# Replicape_B1.net
KiCad netlist of a schematic drawn in EAGLE
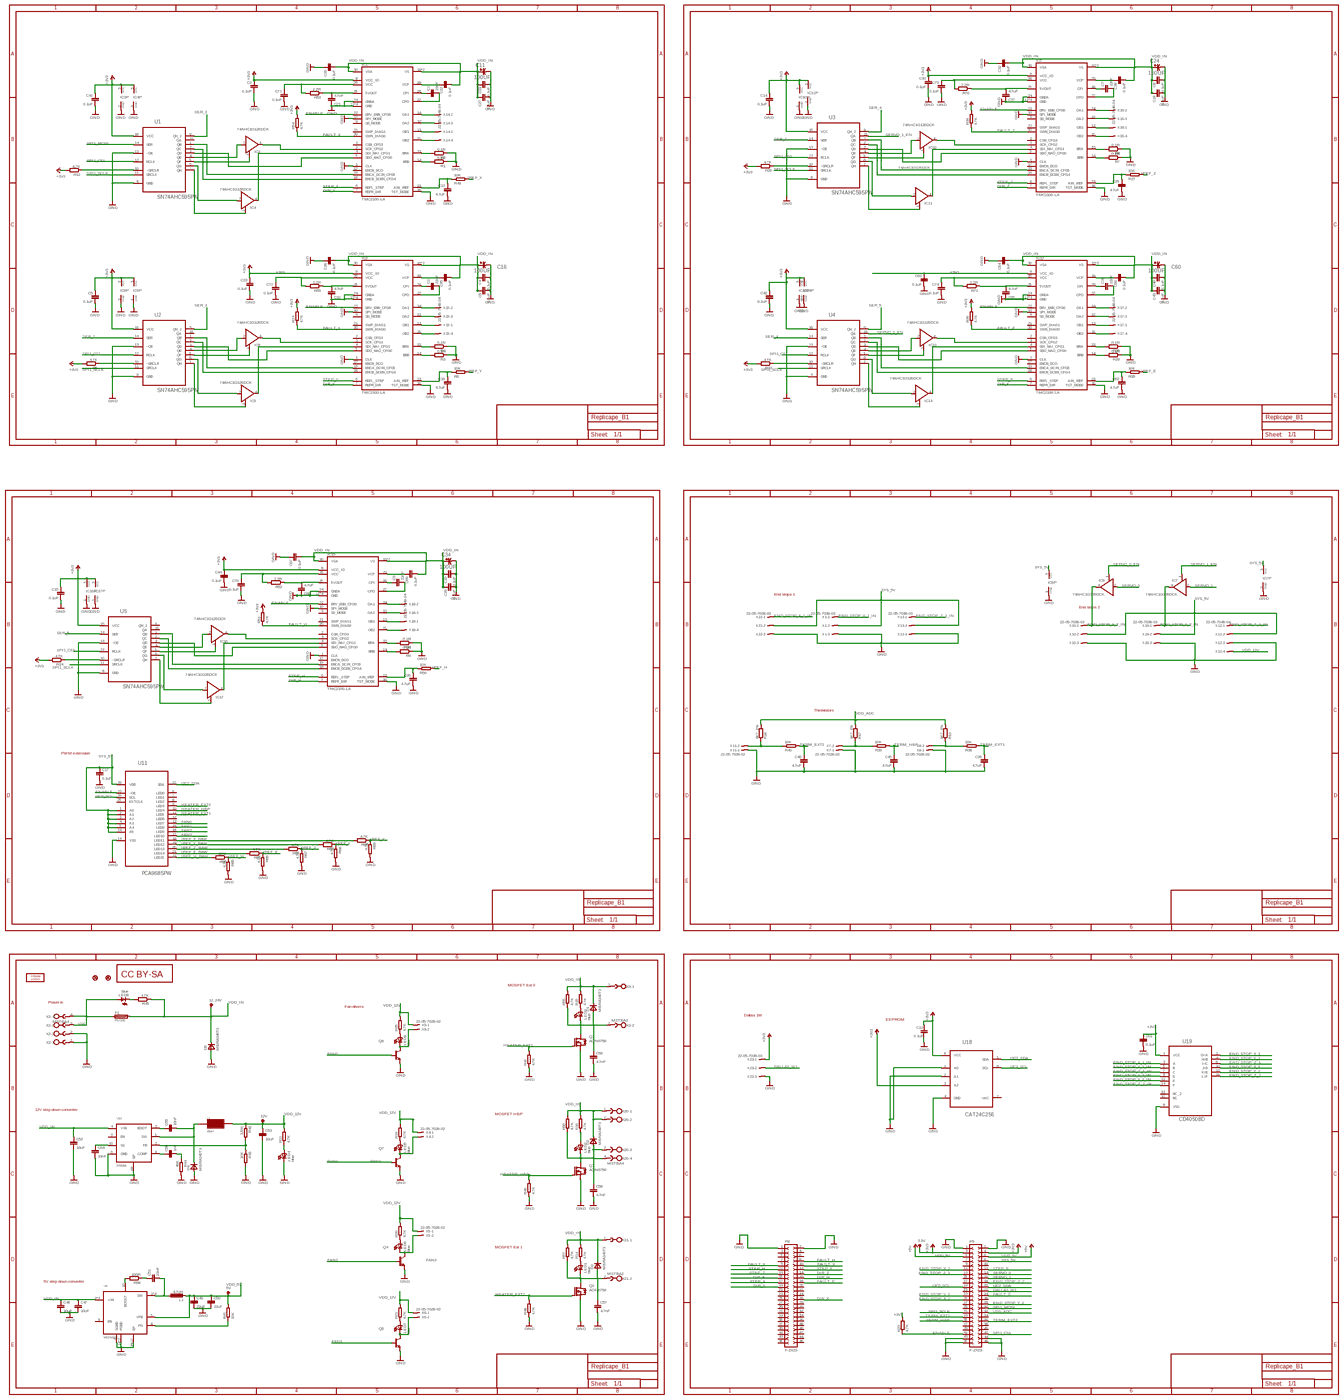
[diagram p0: schematic, sheet 1, overview]
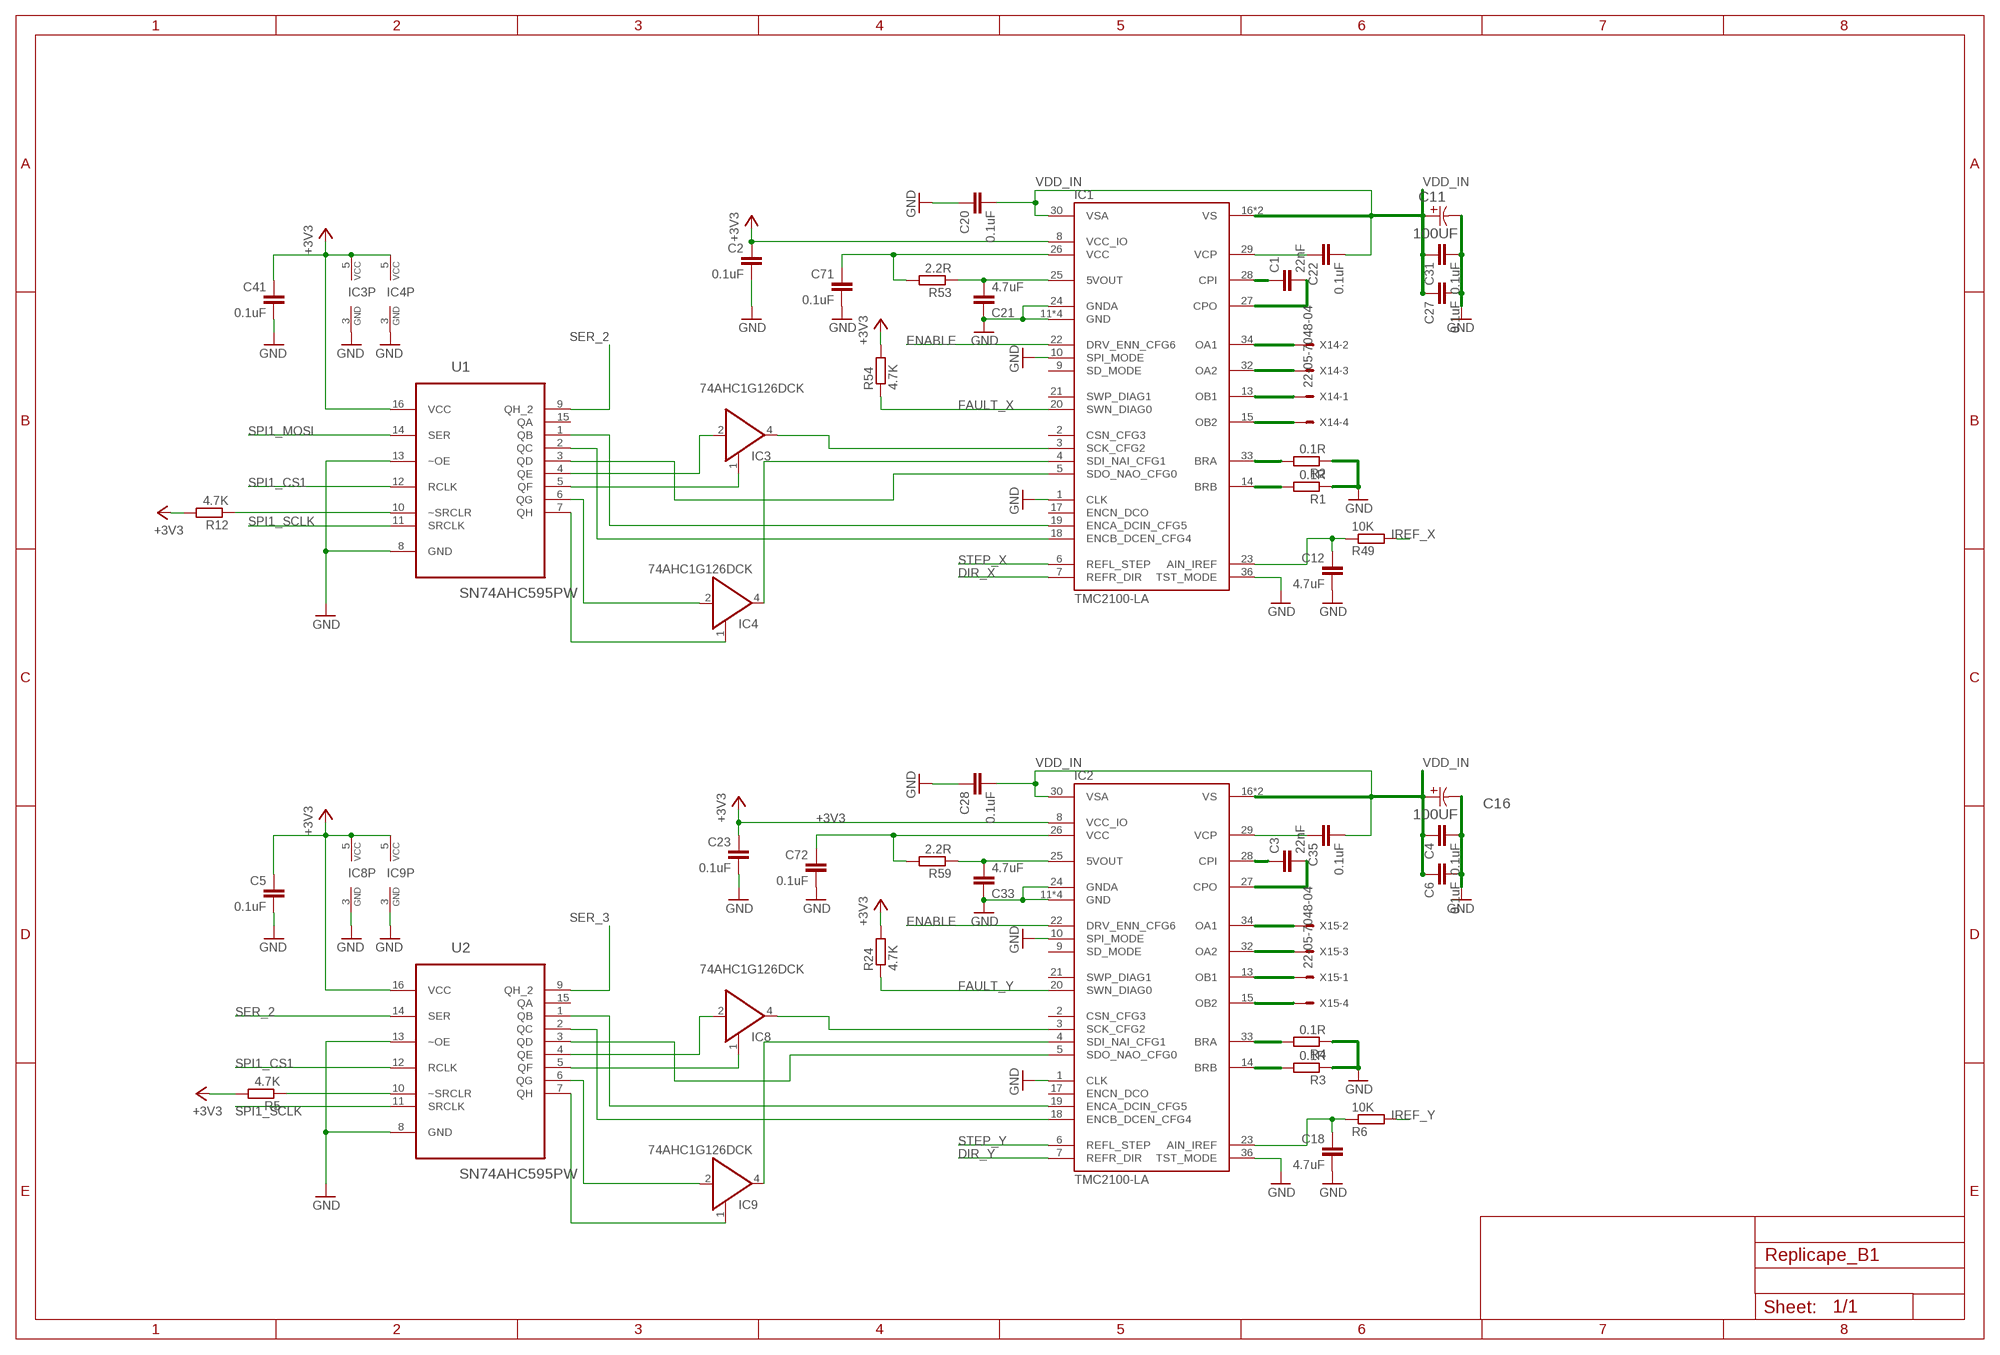
[diagram p1: schematic, sheet 1, part 1 of 4]
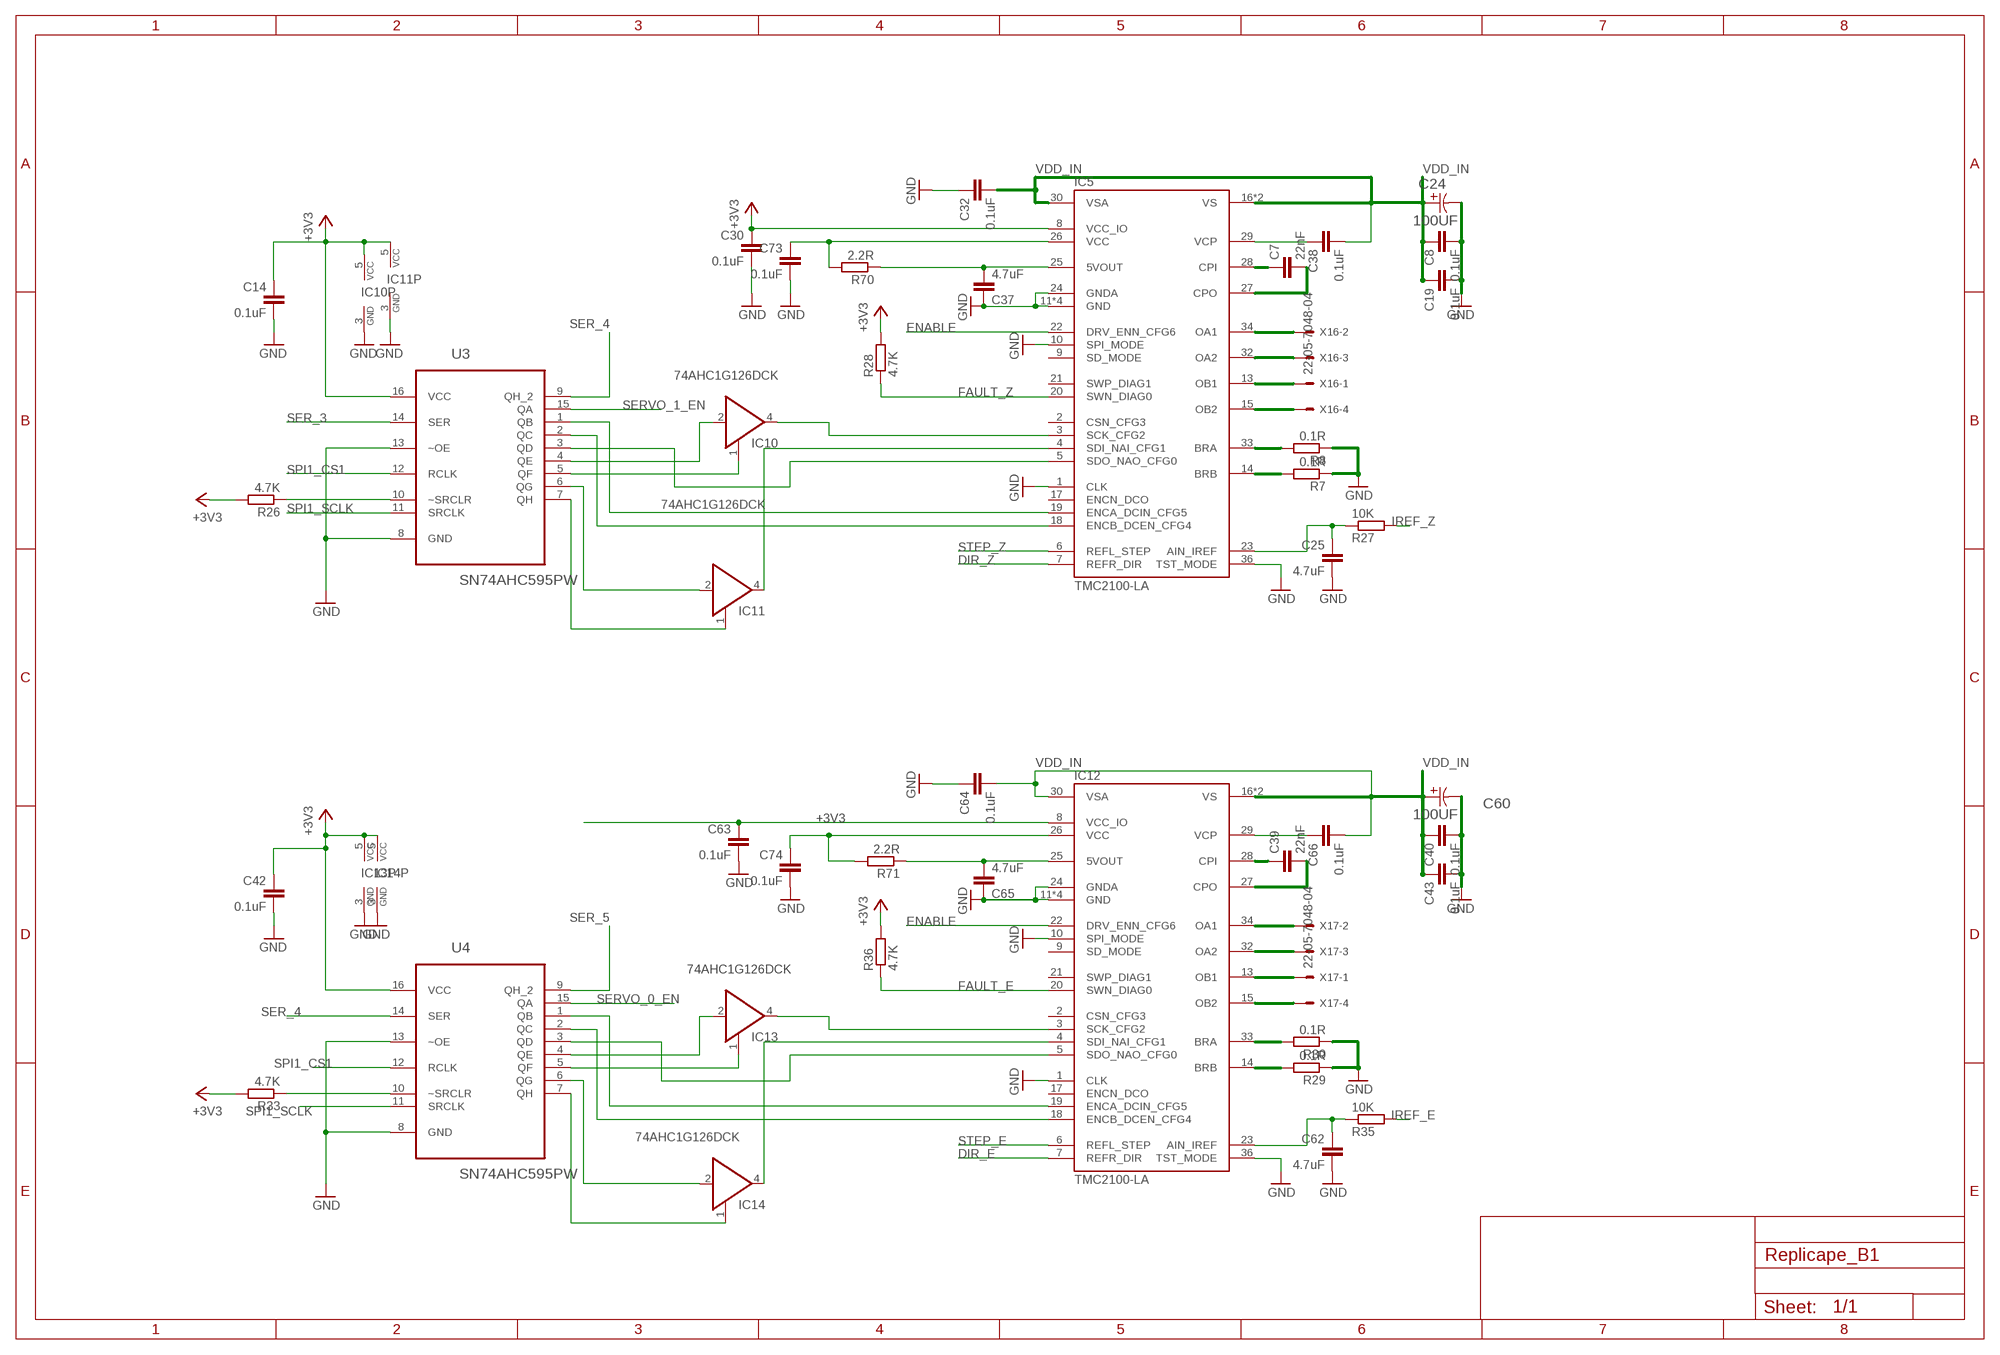
[diagram p2: schematic, sheet 1, part 2 of 4]
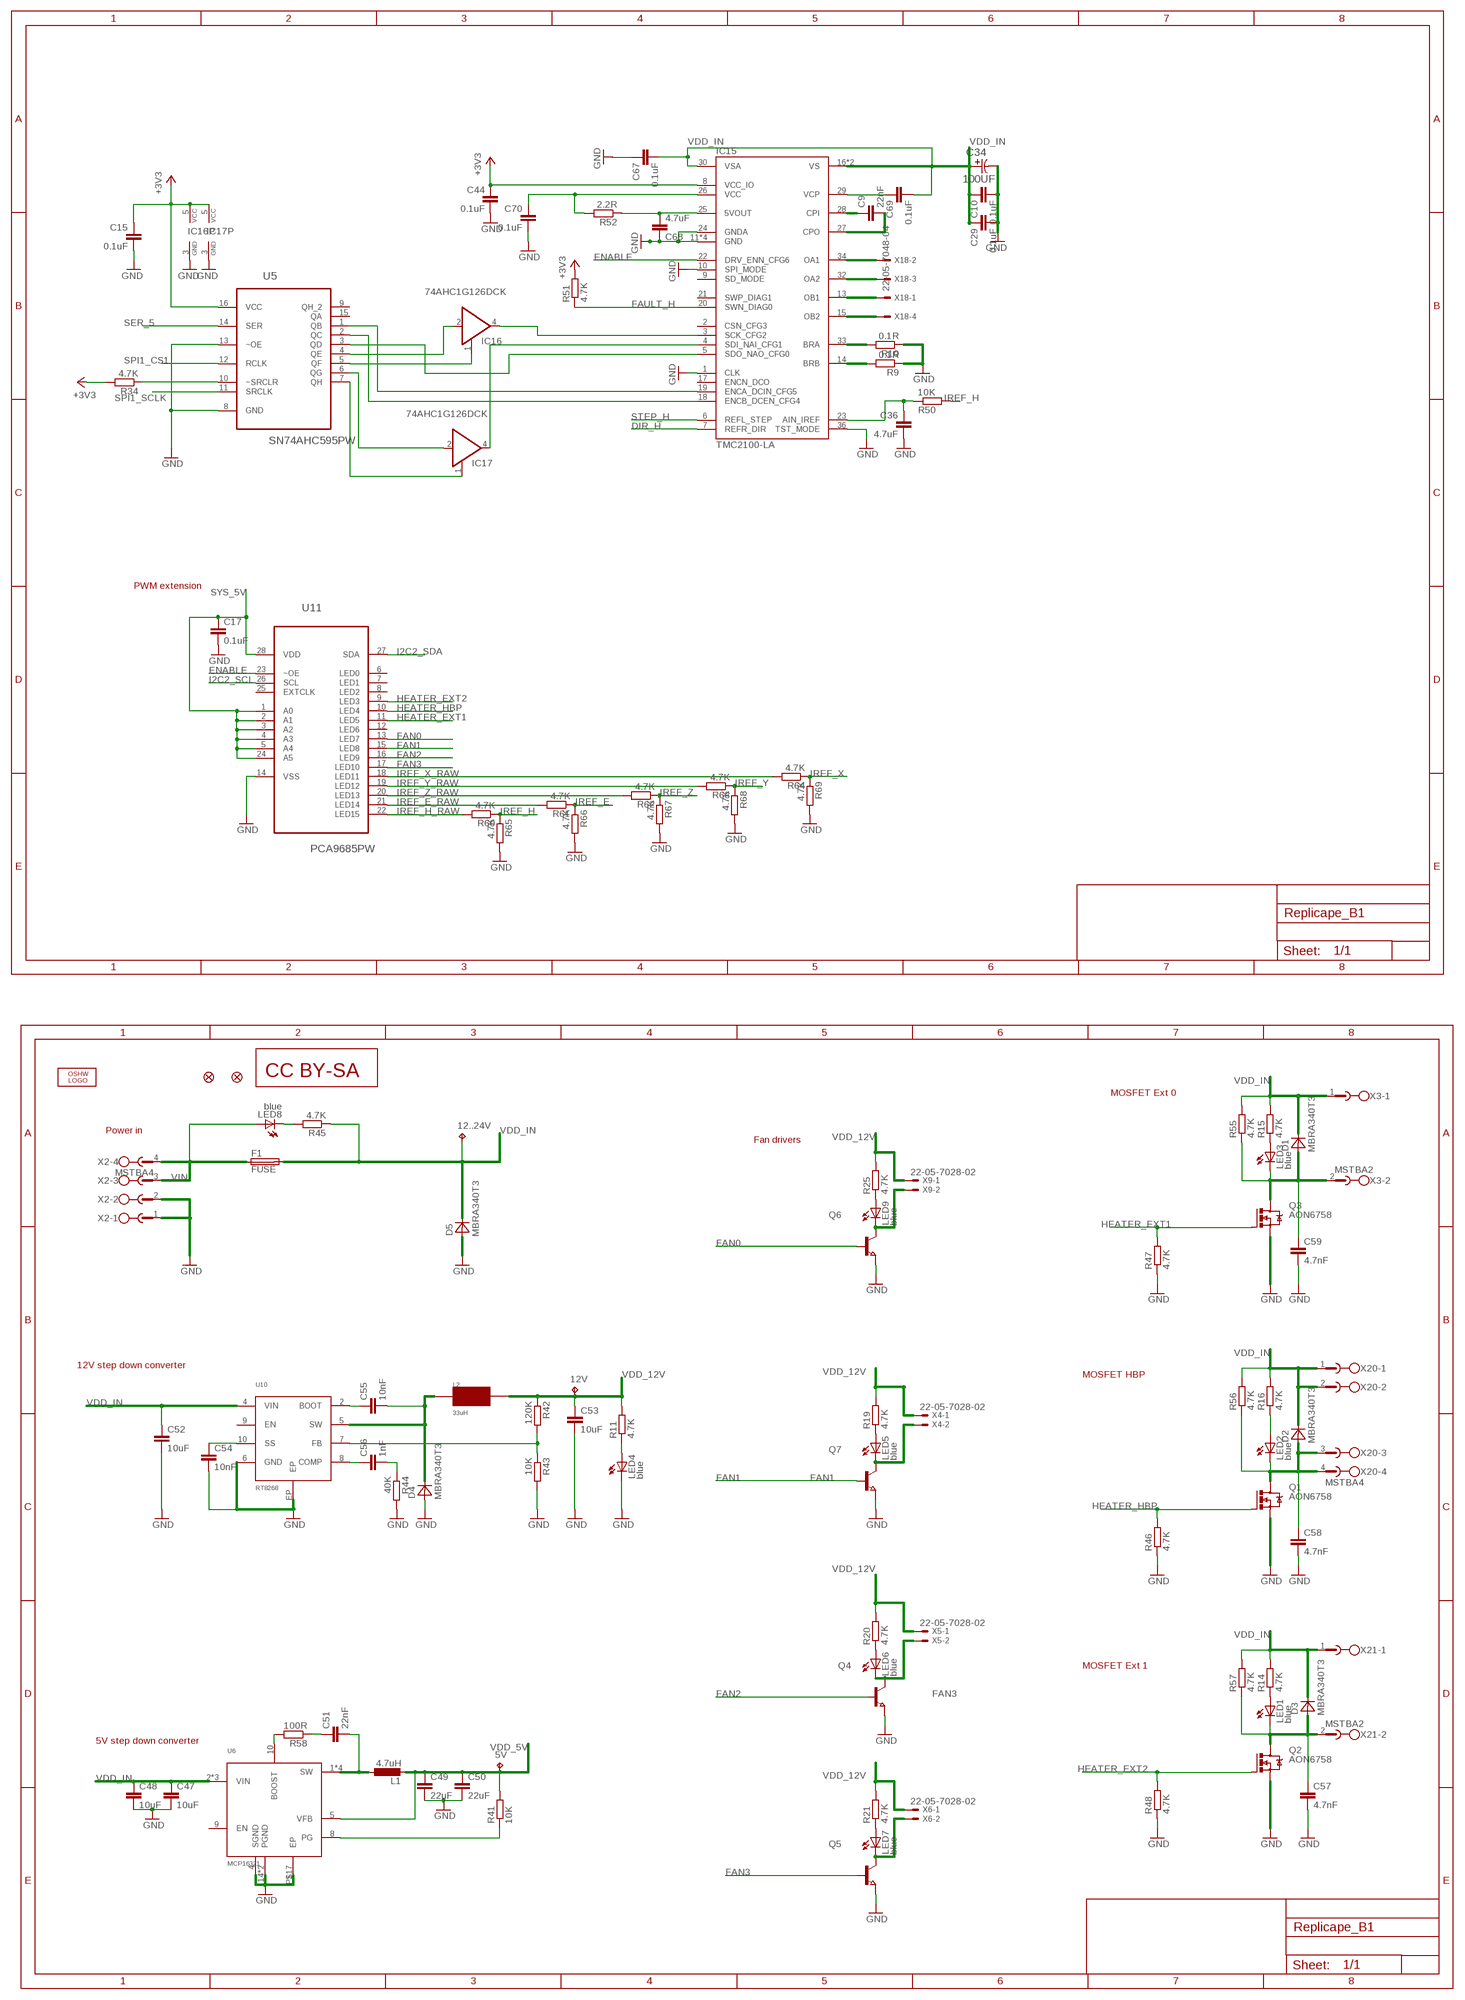
[diagram p3: schematic, sheet 1, part 3 of 4]
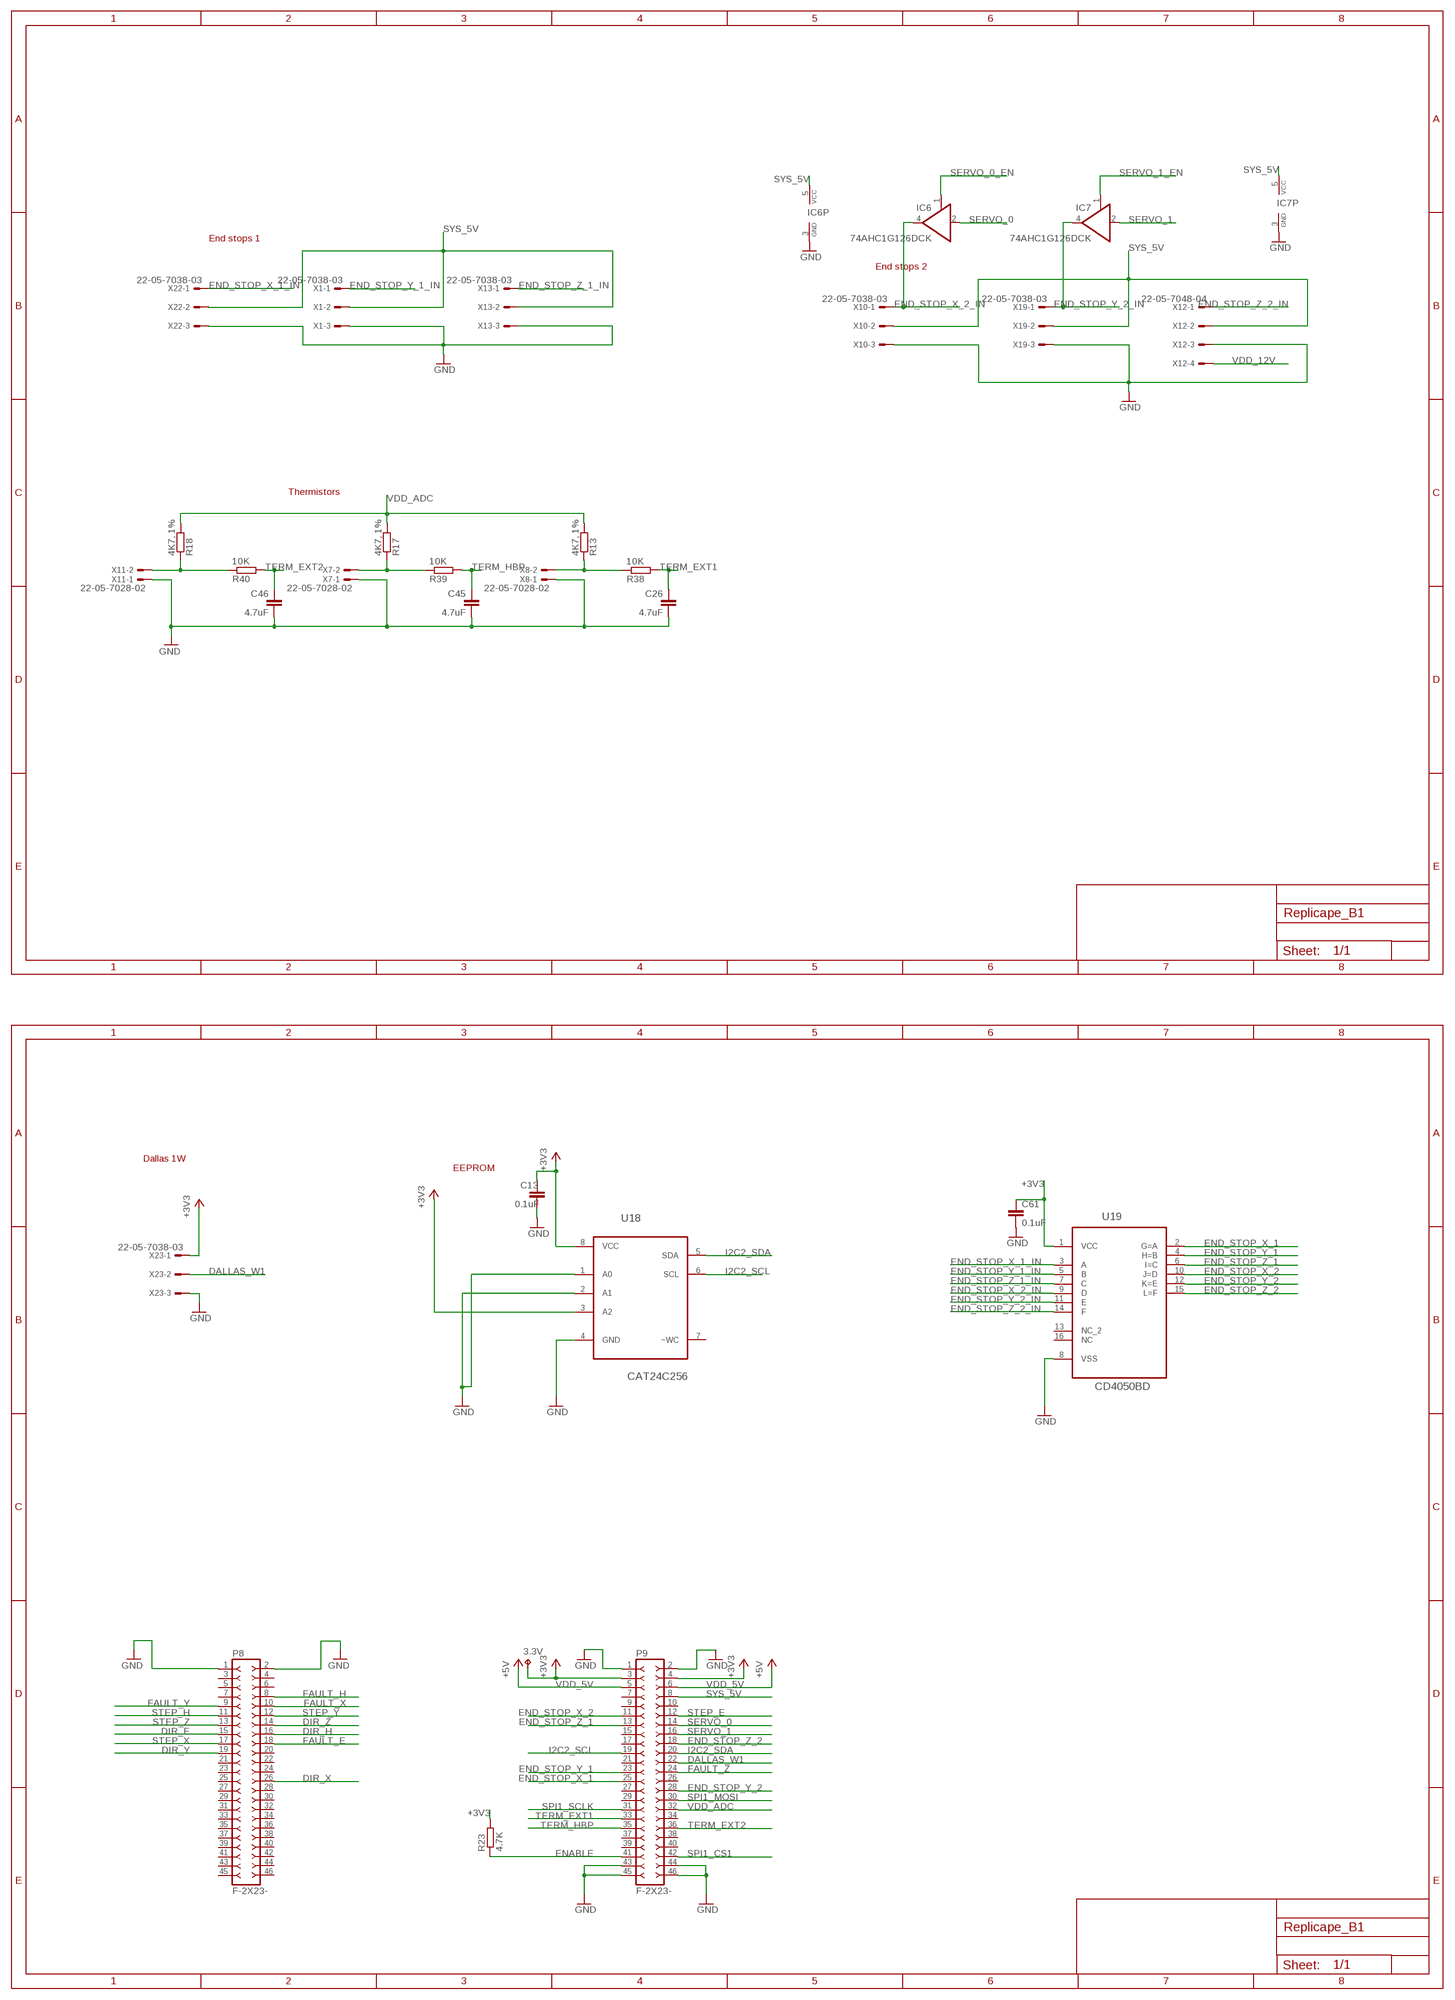
[diagram p4: schematic, sheet 1, part 4 of 4]

(export (version "E")
  (design (tool "Eeschema 10.0.6"))
  (components
    (comp (ref "3.3V")
      (value "TPB1,27")
      (footprint "eagle-import:B1,27")
      (libsource (lib "eagle-import") (part "TPB1,27"))
    )
    (comp (ref "5V")
      (value "TPB1,27")
      (footprint "eagle-import:B1,27")
      (libsource (lib "eagle-import") (part "TPB1,27"))
    )
    (comp (ref "12..24V")
      (value "TPB1,27")
      (footprint "eagle-import:B1,27")
      (libsource (lib "eagle-import") (part "TPB1,27"))
    )
    (comp (ref "12V")
      (value "TPB1,27")
      (footprint "eagle-import:B1,27")
      (libsource (lib "eagle-import") (part "TPB1,27"))
    )
    (comp (ref "C1")
      (value "22nF")
      (footprint "eagle-import:C0402")
      (libsource (lib "eagle-import") (part "C-EUC0402"))
    )
    (comp (ref "C2")
      (value "0.1uF")
      (footprint "eagle-import:C0402")
      (libsource (lib "eagle-import") (part "C-EUC0402"))
    )
    (comp (ref "C3")
      (value "22nF")
      (footprint "eagle-import:C0402")
      (libsource (lib "eagle-import") (part "C-EUC0402"))
    )
    (comp (ref "C4")
      (value "0.1uF")
      (footprint "eagle-import:C0402")
      (libsource (lib "eagle-import") (part "C-EUC0402"))
    )
    (comp (ref "C5")
      (value "0.1uF")
      (footprint "eagle-import:C0402")
      (libsource (lib "eagle-import") (part "C-EUC0402"))
    )
    (comp (ref "C6")
      (value "0.1uF")
      (footprint "eagle-import:C0402")
      (libsource (lib "eagle-import") (part "C-EUC0402"))
    )
    (comp (ref "C7")
      (value "22nF")
      (footprint "eagle-import:C0402")
      (libsource (lib "eagle-import") (part "C-EUC0402"))
    )
    (comp (ref "C8")
      (value "0.1uF")
      (footprint "eagle-import:C0402")
      (libsource (lib "eagle-import") (part "C-EUC0402"))
    )
    (comp (ref "C9")
      (value "22nF")
      (footprint "eagle-import:C0402")
      (libsource (lib "eagle-import") (part "C-EUC0402"))
    )
    (comp (ref "C10")
      (value "0.1uF")
      (footprint "eagle-import:C0402")
      (libsource (lib "eagle-import") (part "C-EUC0402"))
    )
    (comp (ref "C11")
      (value "100UF")
      (footprint "eagle-import:CAPAE660X800N")
      (fields (field (name "MPN") "EEE-FK1V101XP") (field (name "TOLERANCE") "±20 %"))
      (libsource (lib "eagle-import") (part "EEE--CASE-D8FK1V101XP"))
    )
    (comp (ref "C12")
      (value "4.7uF")
      (footprint "eagle-import:C0402")
      (libsource (lib "eagle-import") (part "C-EUC0402"))
    )
    (comp (ref "C13")
      (value "0.1uF")
      (footprint "eagle-import:C0402")
      (libsource (lib "eagle-import") (part "C-EUC0402"))
    )
    (comp (ref "C14")
      (value "0.1uF")
      (footprint "eagle-import:C0402")
      (libsource (lib "eagle-import") (part "C-EUC0402"))
    )
    (comp (ref "C15")
      (value "0.1uF")
      (footprint "eagle-import:C0402")
      (libsource (lib "eagle-import") (part "C-EUC0402"))
    )
    (comp (ref "C16")
      (value "100UF")
      (footprint "eagle-import:CAPAE660X800N")
      (fields (field (name "MPN") "EEE-FK1V101XP") (field (name "TOLERANCE") "±20 %"))
      (libsource (lib "eagle-import") (part "EEE--CASE-D8FK1V101XP"))
    )
    (comp (ref "C17")
      (value "0.1uF")
      (footprint "eagle-import:C0402")
      (libsource (lib "eagle-import") (part "C-EUC0402"))
    )
    (comp (ref "C18")
      (value "4.7uF")
      (footprint "eagle-import:C0402")
      (libsource (lib "eagle-import") (part "C-EUC0402"))
    )
    (comp (ref "C19")
      (value "0.1uF")
      (footprint "eagle-import:C0402")
      (libsource (lib "eagle-import") (part "C-EUC0402"))
    )
    (comp (ref "C20")
      (value "0.1uF")
      (footprint "eagle-import:C0402")
      (libsource (lib "eagle-import") (part "C-EUC0402"))
    )
    (comp (ref "C21")
      (value "4.7uF")
      (footprint "eagle-import:C0402")
      (libsource (lib "eagle-import") (part "C-EUC0402"))
    )
    (comp (ref "C22")
      (value "0.1uF")
      (footprint "eagle-import:C0402")
      (libsource (lib "eagle-import") (part "C-EUC0402"))
    )
    (comp (ref "C23")
      (value "0.1uF")
      (footprint "eagle-import:C0402")
      (libsource (lib "eagle-import") (part "C-EUC0402"))
    )
    (comp (ref "C24")
      (value "100UF")
      (footprint "eagle-import:CAPAE660X800N")
      (fields (field (name "MPN") "EEE-FK1V101XP") (field (name "TOLERANCE") "±20 %"))
      (libsource (lib "eagle-import") (part "EEE--CASE-D8FK1V101XP"))
    )
    (comp (ref "C25")
      (value "4.7uF")
      (footprint "eagle-import:C0402")
      (libsource (lib "eagle-import") (part "C-EUC0402"))
    )
    (comp (ref "C26")
      (value "4.7uF")
      (footprint "eagle-import:C0402")
      (libsource (lib "eagle-import") (part "C-EUC0402"))
    )
    (comp (ref "C27")
      (value "0.1uF")
      (footprint "eagle-import:C0402")
      (libsource (lib "eagle-import") (part "C-EUC0402"))
    )
    (comp (ref "C28")
      (value "0.1uF")
      (footprint "eagle-import:C0402")
      (libsource (lib "eagle-import") (part "C-EUC0402"))
    )
    (comp (ref "C29")
      (value "0.1uF")
      (footprint "eagle-import:C0402")
      (libsource (lib "eagle-import") (part "C-EUC0402"))
    )
    (comp (ref "C30")
      (value "0.1uF")
      (footprint "eagle-import:C0402")
      (libsource (lib "eagle-import") (part "C-EUC0402"))
    )
    (comp (ref "C31")
      (value "0.1uF")
      (footprint "eagle-import:C0402")
      (libsource (lib "eagle-import") (part "C-EUC0402"))
    )
    (comp (ref "C32")
      (value "0.1uF")
      (footprint "eagle-import:C0402")
      (libsource (lib "eagle-import") (part "C-EUC0402"))
    )
    (comp (ref "C33")
      (value "4.7uF")
      (footprint "eagle-import:C0402")
      (libsource (lib "eagle-import") (part "C-EUC0402"))
    )
    (comp (ref "C34")
      (value "100UF")
      (footprint "eagle-import:CAPAE660X800N")
      (fields (field (name "MPN") "EEE-FK1V101XP") (field (name "TOLERANCE") "±20 %"))
      (libsource (lib "eagle-import") (part "EEE--CASE-D8FK1V101XP"))
    )
    (comp (ref "C35")
      (value "0.1uF")
      (footprint "eagle-import:C0402")
      (libsource (lib "eagle-import") (part "C-EUC0402"))
    )
    (comp (ref "C36")
      (value "4.7uF")
      (footprint "eagle-import:C0402")
      (libsource (lib "eagle-import") (part "C-EUC0402"))
    )
    (comp (ref "C37")
      (value "4.7uF")
      (footprint "eagle-import:C0402")
      (libsource (lib "eagle-import") (part "C-EUC0402"))
    )
    (comp (ref "C38")
      (value "0.1uF")
      (footprint "eagle-import:C0402")
      (libsource (lib "eagle-import") (part "C-EUC0402"))
    )
    (comp (ref "C39")
      (value "22nF")
      (footprint "eagle-import:C0402")
      (libsource (lib "eagle-import") (part "C-EUC0402"))
    )
    (comp (ref "C40")
      (value "0.1uF")
      (footprint "eagle-import:C0402")
      (libsource (lib "eagle-import") (part "C-EUC0402"))
    )
    (comp (ref "C41")
      (value "0.1uF")
      (footprint "eagle-import:C0402")
      (libsource (lib "eagle-import") (part "C-EUC0402"))
    )
    (comp (ref "C42")
      (value "0.1uF")
      (footprint "eagle-import:C0402")
      (libsource (lib "eagle-import") (part "C-EUC0402"))
    )
    (comp (ref "C43")
      (value "0.1uF")
      (footprint "eagle-import:C0402")
      (libsource (lib "eagle-import") (part "C-EUC0402"))
    )
    (comp (ref "C44")
      (value "0.1uF")
      (footprint "eagle-import:C0402")
      (libsource (lib "eagle-import") (part "C-EUC0402"))
    )
    (comp (ref "C45")
      (value "4.7uF")
      (footprint "eagle-import:C0402")
      (libsource (lib "eagle-import") (part "C-EUC0402"))
    )
    (comp (ref "C46")
      (value "4.7uF")
      (footprint "eagle-import:C0402")
      (libsource (lib "eagle-import") (part "C-EUC0402"))
    )
    (comp (ref "C47")
      (value "10uF")
      (footprint "eagle-import:C1206")
      (libsource (lib "eagle-import") (part "C-EUC1206"))
    )
    (comp (ref "C48")
      (value "10uF")
      (footprint "eagle-import:C1206")
      (libsource (lib "eagle-import") (part "C-EUC1206"))
    )
    (comp (ref "C49")
      (value "22uF")
      (footprint "eagle-import:C1206")
      (libsource (lib "eagle-import") (part "C-EUC1206"))
    )
    (comp (ref "C50")
      (value "22uF")
      (footprint "eagle-import:C1206")
      (libsource (lib "eagle-import") (part "C-EUC1206"))
    )
    (comp (ref "C51")
      (value "22nF")
      (footprint "eagle-import:C0402")
      (libsource (lib "eagle-import") (part "C-EUC0402"))
    )
    (comp (ref "C52")
      (value "10uF")
      (footprint "eagle-import:C1206")
      (libsource (lib "eagle-import") (part "C-EUC1206"))
    )
    (comp (ref "C53")
      (value "10uF")
      (footprint "eagle-import:C1206")
      (libsource (lib "eagle-import") (part "C-EUC1206"))
    )
    (comp (ref "C54")
      (value "10nF")
      (footprint "eagle-import:C0402")
      (libsource (lib "eagle-import") (part "C-EUC0402"))
    )
    (comp (ref "C55")
      (value "10nF")
      (footprint "eagle-import:C0402")
      (libsource (lib "eagle-import") (part "C-EUC0402"))
    )
    (comp (ref "C56")
      (value "1nF")
      (footprint "eagle-import:C0402")
      (libsource (lib "eagle-import") (part "C-EUC0402"))
    )
    (comp (ref "C57")
      (value "4.7nF")
      (footprint "eagle-import:C0402")
      (libsource (lib "eagle-import") (part "C-EUC0402"))
    )
    (comp (ref "C58")
      (value "4.7nF")
      (footprint "eagle-import:C0402")
      (libsource (lib "eagle-import") (part "C-EUC0402"))
    )
    (comp (ref "C59")
      (value "4.7nF")
      (footprint "eagle-import:C0402")
      (libsource (lib "eagle-import") (part "C-EUC0402"))
    )
    (comp (ref "C60")
      (value "100UF")
      (footprint "eagle-import:CAPAE660X800N")
      (fields (field (name "MPN") "EEE-FK1V101XP") (field (name "TOLERANCE") "±20 %"))
      (libsource (lib "eagle-import") (part "EEE--CASE-D8FK1V101XP"))
    )
    (comp (ref "C61")
      (value "0.1uF")
      (footprint "eagle-import:C0402")
      (libsource (lib "eagle-import") (part "C-EUC0402"))
    )
    (comp (ref "C62")
      (value "4.7uF")
      (footprint "eagle-import:C0402")
      (libsource (lib "eagle-import") (part "C-EUC0402"))
    )
    (comp (ref "C63")
      (value "0.1uF")
      (footprint "eagle-import:C0402")
      (libsource (lib "eagle-import") (part "C-EUC0402"))
    )
    (comp (ref "C64")
      (value "0.1uF")
      (footprint "eagle-import:C0402")
      (libsource (lib "eagle-import") (part "C-EUC0402"))
    )
    (comp (ref "C65")
      (value "4.7uF")
      (footprint "eagle-import:C0402")
      (libsource (lib "eagle-import") (part "C-EUC0402"))
    )
    (comp (ref "C66")
      (value "0.1uF")
      (footprint "eagle-import:C0402")
      (libsource (lib "eagle-import") (part "C-EUC0402"))
    )
    (comp (ref "C67")
      (value "0.1uF")
      (footprint "eagle-import:C0402")
      (libsource (lib "eagle-import") (part "C-EUC0402"))
    )
    (comp (ref "C68")
      (value "4.7uF")
      (footprint "eagle-import:C0402")
      (libsource (lib "eagle-import") (part "C-EUC0402"))
    )
    (comp (ref "C69")
      (value "0.1uF")
      (footprint "eagle-import:C0402")
      (libsource (lib "eagle-import") (part "C-EUC0402"))
    )
    (comp (ref "C70")
      (value "0.1uF")
      (footprint "eagle-import:C0402")
      (libsource (lib "eagle-import") (part "C-EUC0402"))
    )
    (comp (ref "C71")
      (value "0.1uF")
      (footprint "eagle-import:C0402")
      (libsource (lib "eagle-import") (part "C-EUC0402"))
    )
    (comp (ref "C72")
      (value "0.1uF")
      (footprint "eagle-import:C0402")
      (libsource (lib "eagle-import") (part "C-EUC0402"))
    )
    (comp (ref "C73")
      (value "0.1uF")
      (footprint "eagle-import:C0402")
      (libsource (lib "eagle-import") (part "C-EUC0402"))
    )
    (comp (ref "C74")
      (value "0.1uF")
      (footprint "eagle-import:C0402")
      (libsource (lib "eagle-import") (part "C-EUC0402"))
    )
    (comp (ref "D1")
      (value "MBRA340T3")
      (footprint "eagle-import:SMA")
      (libsource (lib "eagle-import") (part "MBRA340T3"))
    )
    (comp (ref "D2")
      (value "MBRA340T3")
      (footprint "eagle-import:SMA")
      (libsource (lib "eagle-import") (part "MBRA340T3"))
    )
    (comp (ref "D3")
      (value "MBRA340T3")
      (footprint "eagle-import:SMA")
      (libsource (lib "eagle-import") (part "MBRA340T3"))
    )
    (comp (ref "D4")
      (value "MBRA340T3")
      (footprint "eagle-import:SMA")
      (libsource (lib "eagle-import") (part "MBRA340T3"))
    )
    (comp (ref "D5")
      (value "MBRA340T3")
      (footprint "eagle-import:SMA")
      (libsource (lib "eagle-import") (part "MBRA340T3"))
    )
    (comp (ref "F1")
      (value "FUSE")
      (footprint "eagle-import:3557")
      (libsource (lib "eagle-import") (part "FUSE"))
    )
    (comp (ref "IC1")
      (value "TMC2100-LA")
      (footprint "eagle-import:QFN36-PAD")
      (libsource (lib "eagle-import") (part "TMC2100-LA"))
    )
    (comp (ref "IC2")
      (value "TMC2100-LA")
      (footprint "eagle-import:QFN36-PAD")
      (libsource (lib "eagle-import") (part "TMC2100-LA"))
    )
    (comp (ref "IC3")
      (value "74AHC1G126DCK")
      (footprint "eagle-import:SC70-5")
      (libsource (lib "eagle-import") (part "741G126DCKAHC"))
    )
    (comp (ref "IC4")
      (value "74AHC1G126DCK")
      (footprint "eagle-import:SC70-5")
      (libsource (lib "eagle-import") (part "741G126DCKAHC"))
    )
    (comp (ref "IC5")
      (value "TMC2100-LA")
      (footprint "eagle-import:QFN36-PAD")
      (libsource (lib "eagle-import") (part "TMC2100-LA"))
    )
    (comp (ref "IC6")
      (value "74AHC1G126DCK")
      (footprint "eagle-import:SC70-5")
      (libsource (lib "eagle-import") (part "741G126DCKAHC"))
    )
    (comp (ref "IC7")
      (value "74AHC1G126DCK")
      (footprint "eagle-import:SC70-5")
      (libsource (lib "eagle-import") (part "741G126DCKAHC"))
    )
    (comp (ref "IC8")
      (value "74AHC1G126DCK")
      (footprint "eagle-import:SC70-5")
      (libsource (lib "eagle-import") (part "741G126DCKAHC"))
    )
    (comp (ref "IC9")
      (value "74AHC1G126DCK")
      (footprint "eagle-import:SC70-5")
      (libsource (lib "eagle-import") (part "741G126DCKAHC"))
    )
    (comp (ref "IC10")
      (value "74AHC1G126DCK")
      (footprint "eagle-import:SC70-5")
      (libsource (lib "eagle-import") (part "741G126DCKAHC"))
    )
    (comp (ref "IC11")
      (value "74AHC1G126DCK")
      (footprint "eagle-import:SC70-5")
      (libsource (lib "eagle-import") (part "741G126DCKAHC"))
    )
    (comp (ref "IC12")
      (value "TMC2100-LA")
      (footprint "eagle-import:QFN36-PAD")
      (libsource (lib "eagle-import") (part "TMC2100-LA"))
    )
    (comp (ref "IC13")
      (value "74AHC1G126DCK")
      (footprint "eagle-import:SC70-5")
      (libsource (lib "eagle-import") (part "741G126DCKAHC"))
    )
    (comp (ref "IC14")
      (value "74AHC1G126DCK")
      (footprint "eagle-import:SC70-5")
      (libsource (lib "eagle-import") (part "741G126DCKAHC"))
    )
    (comp (ref "IC15")
      (value "TMC2100-LA")
      (footprint "eagle-import:QFN36-PAD")
      (libsource (lib "eagle-import") (part "TMC2100-LA"))
    )
    (comp (ref "IC16")
      (value "74AHC1G126DCK")
      (footprint "eagle-import:SC70-5")
      (libsource (lib "eagle-import") (part "741G126DCKAHC"))
    )
    (comp (ref "IC17")
      (value "74AHC1G126DCK")
      (footprint "eagle-import:SC70-5")
      (libsource (lib "eagle-import") (part "741G126DCKAHC"))
    )
    (comp (ref "JP1")
      (value "FIDUCIAL1X2.5")
      (footprint "eagle-import:FIDUCIAL-1X2.5")
      (libsource (lib "eagle-import") (part "FIDUCIAL1X2.5"))
    )
    (comp (ref "JP2")
      (value "FIDUCIAL1X2.5")
      (footprint "eagle-import:FIDUCIAL-1X2.5")
      (libsource (lib "eagle-import") (part "FIDUCIAL1X2.5"))
    )
    (comp (ref "L1")
      (value "4.7uH")
      (footprint "eagle-import:VLC5020")
      (libsource (lib "eagle-import") (part "L-EU"))
    )
    (comp (ref "L2")
      (value "33uH")
      (footprint "eagle-import:NR8040T330")
      (libsource (lib "eagle-import") (part "RT8040T330"))
    )
    (comp (ref "LED1")
      (value "blue")
      (footprint "eagle-import:CHIP-LED0603")
      (libsource (lib "eagle-import") (part "LEDCHIP-LED0603"))
    )
    (comp (ref "LED2")
      (value "blue")
      (footprint "eagle-import:CHIP-LED0603")
      (libsource (lib "eagle-import") (part "LEDCHIP-LED0603"))
    )
    (comp (ref "LED3")
      (value "blue")
      (footprint "eagle-import:CHIP-LED0603")
      (libsource (lib "eagle-import") (part "LEDCHIP-LED0603"))
    )
    (comp (ref "LED4")
      (value "blue")
      (footprint "eagle-import:CHIP-LED0603")
      (libsource (lib "eagle-import") (part "LEDCHIP-LED0603"))
    )
    (comp (ref "LED5")
      (value "blue")
      (footprint "eagle-import:CHIP-LED0603")
      (libsource (lib "eagle-import") (part "LEDCHIP-LED0603"))
    )
    (comp (ref "LED6")
      (value "blue")
      (footprint "eagle-import:CHIP-LED0603")
      (libsource (lib "eagle-import") (part "LEDCHIP-LED0603"))
    )
    (comp (ref "LED7")
      (value "blue")
      (footprint "eagle-import:CHIP-LED0603")
      (libsource (lib "eagle-import") (part "LEDCHIP-LED0603"))
    )
    (comp (ref "LED8")
      (value "blue")
      (footprint "eagle-import:CHIP-LED0603")
      (libsource (lib "eagle-import") (part "LEDCHIP-LED0603"))
    )
    (comp (ref "LED9")
      (value "blue")
      (footprint "eagle-import:CHIP-LED0603")
      (libsource (lib "eagle-import") (part "LEDCHIP-LED0603"))
    )
    (comp (ref "LOGO1")
      (value "OSHW_LOGO_FILLX0200-NT")
      (footprint "eagle-import:OSHW_FILLX200_NOTEXT")
      (libsource (lib "eagle-import") (part "OSHW_LOGO_FILLX0200-NT"))
    )
    (comp (ref "P8")
      (value "F-2X23-")
      (footprint "eagle-import:DIL-100-2X23")
      (libsource (lib "eagle-import") (part "F-2X23-"))
    )
    (comp (ref "P9")
      (value "F-2X23-")
      (footprint "eagle-import:DIL-100-2X23")
      (libsource (lib "eagle-import") (part "F-2X23-"))
    )
    (comp (ref "Q1")
      (value "AON6758")
      (footprint "eagle-import:8-DFN-EP-(5X6)")
      (libsource (lib "eagle-import") (part "AON6758"))
    )
    (comp (ref "Q2")
      (value "AON6758")
      (footprint "eagle-import:8-DFN-EP-(5X6)")
      (libsource (lib "eagle-import") (part "AON6758"))
    )
    (comp (ref "Q3")
      (value "AON6758")
      (footprint "eagle-import:8-DFN-EP-(5X6)")
      (libsource (lib "eagle-import") (part "AON6758"))
    )
    (comp (ref "Q4")
      (value "NPN-TRANSISTOR_SOT23")
      (footprint "eagle-import:SOT23")
      (libsource (lib "eagle-import") (part "NPN-TRANSISTOR_SOT23"))
    )
    (comp (ref "Q5")
      (value "NPN-TRANSISTOR_SOT23")
      (footprint "eagle-import:SOT23")
      (libsource (lib "eagle-import") (part "NPN-TRANSISTOR_SOT23"))
    )
    (comp (ref "Q6")
      (value "NPN-TRANSISTOR_SOT23")
      (footprint "eagle-import:SOT23")
      (libsource (lib "eagle-import") (part "NPN-TRANSISTOR_SOT23"))
    )
    (comp (ref "Q7")
      (value "NPN-TRANSISTOR_SOT23")
      (footprint "eagle-import:SOT23")
      (libsource (lib "eagle-import") (part "NPN-TRANSISTOR_SOT23"))
    )
    (comp (ref "R1")
      (value "0.1R")
      (footprint "eagle-import:R0805")
      (libsource (lib "eagle-import") (part "R-EU_R0805"))
    )
    (comp (ref "R2")
      (value "0.1R")
      (footprint "eagle-import:R0805")
      (libsource (lib "eagle-import") (part "R-EU_R0805"))
    )
    (comp (ref "R3")
      (value "0.1R")
      (footprint "eagle-import:R0805")
      (libsource (lib "eagle-import") (part "R-EU_R0805"))
    )
    (comp (ref "R4")
      (value "0.1R")
      (footprint "eagle-import:R0805")
      (libsource (lib "eagle-import") (part "R-EU_R0805"))
    )
    (comp (ref "R5")
      (value "4.7K")
      (footprint "eagle-import:R0402")
      (libsource (lib "eagle-import") (part "R-EU_R0402"))
    )
    (comp (ref "R6")
      (value "10K")
      (footprint "eagle-import:R0402")
      (libsource (lib "eagle-import") (part "R-EU_R0402"))
    )
    (comp (ref "R7")
      (value "0.1R")
      (footprint "eagle-import:R0805")
      (libsource (lib "eagle-import") (part "R-EU_R0805"))
    )
    (comp (ref "R8")
      (value "0.1R")
      (footprint "eagle-import:R0805")
      (libsource (lib "eagle-import") (part "R-EU_R0805"))
    )
    (comp (ref "R9")
      (value "0.1R")
      (footprint "eagle-import:R0805")
      (libsource (lib "eagle-import") (part "R-EU_R0805"))
    )
    (comp (ref "R10")
      (value "0.1R")
      (footprint "eagle-import:R0805")
      (libsource (lib "eagle-import") (part "R-EU_R0805"))
    )
    (comp (ref "R11")
      (value "4.7K")
      (footprint "eagle-import:R0402")
      (libsource (lib "eagle-import") (part "R-EU_R0402"))
    )
    (comp (ref "R12")
      (value "4.7K")
      (footprint "eagle-import:R0402")
      (libsource (lib "eagle-import") (part "R-EU_R0402"))
    )
    (comp (ref "R13")
      (value "4K7, 1%")
      (footprint "eagle-import:R0402")
      (libsource (lib "eagle-import") (part "R-EU_R0402"))
    )
    (comp (ref "R14")
      (value "4.7K")
      (footprint "eagle-import:R0402")
      (libsource (lib "eagle-import") (part "R-EU_R0402"))
    )
    (comp (ref "R15")
      (value "4.7K")
      (footprint "eagle-import:R0402")
      (libsource (lib "eagle-import") (part "R-EU_R0402"))
    )
    (comp (ref "R16")
      (value "4.7K")
      (footprint "eagle-import:R0402")
      (libsource (lib "eagle-import") (part "R-EU_R0402"))
    )
    (comp (ref "R17")
      (value "4K7, 1%")
      (footprint "eagle-import:R0402")
      (libsource (lib "eagle-import") (part "R-EU_R0402"))
    )
    (comp (ref "R18")
      (value "4K7, 1%")
      (footprint "eagle-import:R0402")
      (libsource (lib "eagle-import") (part "R-EU_R0402"))
    )
    (comp (ref "R19")
      (value "4.7K")
      (footprint "eagle-import:R0402")
      (libsource (lib "eagle-import") (part "R-EU_R0402"))
    )
    (comp (ref "R20")
      (value "4.7K")
      (footprint "eagle-import:R0402")
      (libsource (lib "eagle-import") (part "R-EU_R0402"))
    )
    (comp (ref "R21")
      (value "4.7K")
      (footprint "eagle-import:R0402")
      (libsource (lib "eagle-import") (part "R-EU_R0402"))
    )
    (comp (ref "R23")
      (value "4.7K")
      (footprint "eagle-import:R0402")
      (libsource (lib "eagle-import") (part "R-EU_R0402"))
    )
    (comp (ref "R24")
      (value "4.7K")
      (footprint "eagle-import:R0402")
      (libsource (lib "eagle-import") (part "R-EU_R0402"))
    )
    (comp (ref "R25")
      (value "4.7K")
      (footprint "eagle-import:R0402")
      (libsource (lib "eagle-import") (part "R-EU_R0402"))
    )
    (comp (ref "R26")
      (value "4.7K")
      (footprint "eagle-import:R0402")
      (libsource (lib "eagle-import") (part "R-EU_R0402"))
    )
    (comp (ref "R27")
      (value "10K")
      (footprint "eagle-import:R0402")
      (libsource (lib "eagle-import") (part "R-EU_R0402"))
    )
    (comp (ref "R28")
      (value "4.7K")
      (footprint "eagle-import:R0402")
      (libsource (lib "eagle-import") (part "R-EU_R0402"))
    )
    (comp (ref "R29")
      (value "0.1R")
      (footprint "eagle-import:R0805")
      (libsource (lib "eagle-import") (part "R-EU_R0805"))
    )
    (comp (ref "R30")
      (value "0.1R")
      (footprint "eagle-import:R0805")
      (libsource (lib "eagle-import") (part "R-EU_R0805"))
    )
    (comp (ref "R33")
      (value "4.7K")
      (footprint "eagle-import:R0402")
      (libsource (lib "eagle-import") (part "R-EU_R0402"))
    )
    (comp (ref "R34")
      (value "4.7K")
      (footprint "eagle-import:R0402")
      (libsource (lib "eagle-import") (part "R-EU_R0402"))
    )
    (comp (ref "R35")
      (value "10K")
      (footprint "eagle-import:R0402")
      (libsource (lib "eagle-import") (part "R-EU_R0402"))
    )
    (comp (ref "R36")
      (value "4.7K")
      (footprint "eagle-import:R0402")
      (libsource (lib "eagle-import") (part "R-EU_R0402"))
    )
    (comp (ref "R38")
      (value "10K")
      (footprint "eagle-import:R0402")
      (libsource (lib "eagle-import") (part "R-EU_R0402"))
    )
    (comp (ref "R39")
      (value "10K")
      (footprint "eagle-import:R0402")
      (libsource (lib "eagle-import") (part "R-EU_R0402"))
    )
    (comp (ref "R40")
      (value "10K")
      (footprint "eagle-import:R0402")
      (libsource (lib "eagle-import") (part "R-EU_R0402"))
    )
    (comp (ref "R41")
      (value "10K")
      (footprint "eagle-import:R0402")
      (libsource (lib "eagle-import") (part "R-EU_R0402"))
    )
    (comp (ref "R42")
      (value "120K")
      (footprint "eagle-import:R0402")
      (libsource (lib "eagle-import") (part "R-EU_R0402"))
    )
    (comp (ref "R43")
      (value "10K")
      (footprint "eagle-import:R0402")
      (libsource (lib "eagle-import") (part "R-EU_R0402"))
    )
    (comp (ref "R44")
      (value "40K")
      (footprint "eagle-import:R0402")
      (libsource (lib "eagle-import") (part "R-EU_R0402"))
    )
    (comp (ref "R45")
      (value "4.7K")
      (footprint "eagle-import:R0402")
      (libsource (lib "eagle-import") (part "R-EU_R0402"))
    )
    (comp (ref "R46")
      (value "4.7K")
      (footprint "eagle-import:R0402")
      (libsource (lib "eagle-import") (part "R-EU_R0402"))
    )
    (comp (ref "R47")
      (value "4.7K")
      (footprint "eagle-import:R0402")
      (libsource (lib "eagle-import") (part "R-EU_R0402"))
    )
    (comp (ref "R48")
      (value "4.7K")
      (footprint "eagle-import:R0402")
      (libsource (lib "eagle-import") (part "R-EU_R0402"))
    )
    (comp (ref "R49")
      (value "10K")
      (footprint "eagle-import:R0402")
      (libsource (lib "eagle-import") (part "R-EU_R0402"))
    )
    (comp (ref "R50")
      (value "10K")
      (footprint "eagle-import:R0402")
      (libsource (lib "eagle-import") (part "R-EU_R0402"))
    )
    (comp (ref "R51")
      (value "4.7K")
      (footprint "eagle-import:R0402")
      (libsource (lib "eagle-import") (part "R-EU_R0402"))
    )
    (comp (ref "R52")
      (value "2.2R")
      (footprint "eagle-import:R0402")
      (libsource (lib "eagle-import") (part "R-EU_R0402"))
    )
    (comp (ref "R53")
      (value "2.2R")
      (footprint "eagle-import:R0402")
      (libsource (lib "eagle-import") (part "R-EU_R0402"))
    )
    (comp (ref "R54")
      (value "4.7K")
      (footprint "eagle-import:R0402")
      (libsource (lib "eagle-import") (part "R-EU_R0402"))
    )
    (comp (ref "R55")
      (value "4.7K")
      (footprint "eagle-import:R0402")
      (libsource (lib "eagle-import") (part "R-EU_R0402"))
    )
    (comp (ref "R56")
      (value "4.7K")
      (footprint "eagle-import:R0402")
      (libsource (lib "eagle-import") (part "R-EU_R0402"))
    )
    (comp (ref "R57")
      (value "4.7K")
      (footprint "eagle-import:R0402")
      (libsource (lib "eagle-import") (part "R-EU_R0402"))
    )
    (comp (ref "R58")
      (value "100R")
      (footprint "eagle-import:R0402")
      (libsource (lib "eagle-import") (part "R-EU_R0402"))
    )
    (comp (ref "R59")
      (value "2.2R")
      (footprint "eagle-import:R0402")
      (libsource (lib "eagle-import") (part "R-EU_R0402"))
    )
    (comp (ref "R60")
      (value "4.7K")
      (footprint "eagle-import:R0402")
      (libsource (lib "eagle-import") (part "R-EU_R0402"))
    )
    (comp (ref "R61")
      (value "4.7K")
      (footprint "eagle-import:R0402")
      (libsource (lib "eagle-import") (part "R-EU_R0402"))
    )
    (comp (ref "R62")
      (value "4.7K")
      (footprint "eagle-import:R0402")
      (libsource (lib "eagle-import") (part "R-EU_R0402"))
    )
    (comp (ref "R63")
      (value "4.7K")
      (footprint "eagle-import:R0402")
      (libsource (lib "eagle-import") (part "R-EU_R0402"))
    )
    (comp (ref "R64")
      (value "4.7K")
      (footprint "eagle-import:R0402")
      (libsource (lib "eagle-import") (part "R-EU_R0402"))
    )
    (comp (ref "R65")
      (value "4.7K")
      (footprint "eagle-import:R0402")
      (libsource (lib "eagle-import") (part "R-EU_R0402"))
    )
    (comp (ref "R66")
      (value "4.7K")
      (footprint "eagle-import:R0402")
      (libsource (lib "eagle-import") (part "R-EU_R0402"))
    )
    (comp (ref "R67")
      (value "4.7K")
      (footprint "eagle-import:R0402")
      (libsource (lib "eagle-import") (part "R-EU_R0402"))
    )
    (comp (ref "R68")
      (value "4.7K")
      (footprint "eagle-import:R0402")
      (libsource (lib "eagle-import") (part "R-EU_R0402"))
    )
    (comp (ref "R69")
      (value "4.7K")
      (footprint "eagle-import:R0402")
      (libsource (lib "eagle-import") (part "R-EU_R0402"))
    )
    (comp (ref "R70")
      (value "2.2R")
      (footprint "eagle-import:R0402")
      (libsource (lib "eagle-import") (part "R-EU_R0402"))
    )
    (comp (ref "R71")
      (value "2.2R")
      (footprint "eagle-import:R0402")
      (libsource (lib "eagle-import") (part "R-EU_R0402"))
    )
    (comp (ref "U$3")
      (value "CC-BY-SA")
      (footprint "eagle-import:CC-BY-SA")
      (libsource (lib "eagle-import") (part "CC-BY-SA"))
    )
    (comp (ref "U1")
      (value "SN74AHC595PW")
      (footprint "eagle-import:SOP65P640X120-16N")
      (libsource (lib "eagle-import") (part "SN74AHC595PW"))
    )
    (comp (ref "U2")
      (value "SN74AHC595PW")
      (footprint "eagle-import:SOP65P640X120-16N")
      (libsource (lib "eagle-import") (part "SN74AHC595PW"))
    )
    (comp (ref "U3")
      (value "SN74AHC595PW")
      (footprint "eagle-import:SOP65P640X120-16N")
      (libsource (lib "eagle-import") (part "SN74AHC595PW"))
    )
    (comp (ref "U4")
      (value "SN74AHC595PW")
      (footprint "eagle-import:SOP65P640X120-16N")
      (libsource (lib "eagle-import") (part "SN74AHC595PW"))
    )
    (comp (ref "U5")
      (value "SN74AHC595PW")
      (footprint "eagle-import:SOP65P640X120-16N")
      (libsource (lib "eagle-import") (part "SN74AHC595PW"))
    )
    (comp (ref "U6")
      (value "MCP16321")
      (footprint "eagle-import:QFN-16")
      (libsource (lib "eagle-import") (part "MCP16321"))
    )
    (comp (ref "U10")
      (value "RT8268")
      (footprint "eagle-import:MSOP10")
      (libsource (lib "eagle-import") (part "RT8268"))
    )
    (comp (ref "U11")
      (value "PCA9685PW")
      (footprint "eagle-import:SOP65P640X110-28N")
      (libsource (lib "eagle-import") (part "PCA9685PW"))
    )
    (comp (ref "U18")
      (value "CAT24C256")
      (footprint "eagle-import:SOIC127P600X175-8N")
      (libsource (lib "eagle-import") (part "CAT24C256"))
    )
    (comp (ref "U19")
      (value "CD4050BD")
      (footprint "eagle-import:SOIC127P600X175-16N")
      (libsource (lib "eagle-import") (part "CD4050BD"))
    )
    (comp (ref "X1")
      (value "22-05-7038-03")
      (footprint "eagle-import:7395-03")
      (libsource (lib "eagle-import") (part "22-?-0305-7038"))
    )
    (comp (ref "X2")
      (value "MSTBA4")
      (footprint "eagle-import:MSTBA4")
      (fields (field (name "MF") "FARNELL") (field (name "MPN") "1757268"))
      (libsource (lib "eagle-import") (part "MSTBA4"))
    )
    (comp (ref "X3")
      (value "MSTBA2")
      (footprint "eagle-import:MSTBA2")
      (fields (field (name "MF") "FARNELL") (field (name "MPN") "1757242"))
      (libsource (lib "eagle-import") (part "MSTBA2"))
    )
    (comp (ref "X4")
      (value "22-05-7028-02")
      (footprint "eagle-import:7395-02")
      (libsource (lib "eagle-import") (part "22-?-0205-7028"))
    )
    (comp (ref "X5")
      (value "22-05-7028-02")
      (footprint "eagle-import:7395-02")
      (libsource (lib "eagle-import") (part "22-?-0205-7028"))
    )
    (comp (ref "X6")
      (value "22-05-7028-02")
      (footprint "eagle-import:7395-02")
      (libsource (lib "eagle-import") (part "22-?-0205-7028"))
    )
    (comp (ref "X7")
      (value "22-05-7028-02")
      (footprint "eagle-import:7395-02")
      (libsource (lib "eagle-import") (part "22-?-0205-7028"))
    )
    (comp (ref "X8")
      (value "22-05-7028-02")
      (footprint "eagle-import:7395-02")
      (libsource (lib "eagle-import") (part "22-?-0205-7028"))
    )
    (comp (ref "X9")
      (value "22-05-7028-02")
      (footprint "eagle-import:7395-02")
      (libsource (lib "eagle-import") (part "22-?-0205-7028"))
    )
    (comp (ref "X10")
      (value "22-05-7038-03")
      (footprint "eagle-import:7395-03")
      (libsource (lib "eagle-import") (part "22-?-0305-7038"))
    )
    (comp (ref "X11")
      (value "22-05-7028-02")
      (footprint "eagle-import:7395-02")
      (libsource (lib "eagle-import") (part "22-?-0205-7028"))
    )
    (comp (ref "X12")
      (value "22-05-7048-04")
      (footprint "eagle-import:7395-04")
      (libsource (lib "eagle-import") (part "22-?-0405-7048"))
    )
    (comp (ref "X13")
      (value "22-05-7038-03")
      (footprint "eagle-import:7395-03")
      (libsource (lib "eagle-import") (part "22-?-0305-7038"))
    )
    (comp (ref "X14")
      (value "22-05-7048-04")
      (footprint "eagle-import:7395-04")
      (libsource (lib "eagle-import") (part "22-?-0405-7048"))
    )
    (comp (ref "X15")
      (value "22-05-7048-04")
      (footprint "eagle-import:7395-04")
      (libsource (lib "eagle-import") (part "22-?-0405-7048"))
    )
    (comp (ref "X16")
      (value "22-05-7048-04")
      (footprint "eagle-import:7395-04")
      (libsource (lib "eagle-import") (part "22-?-0405-7048"))
    )
    (comp (ref "X17")
      (value "22-05-7048-04")
      (footprint "eagle-import:7395-04")
      (libsource (lib "eagle-import") (part "22-?-0405-7048"))
    )
    (comp (ref "X18")
      (value "22-05-7048-04")
      (footprint "eagle-import:7395-04")
      (libsource (lib "eagle-import") (part "22-?-0405-7048"))
    )
    (comp (ref "X19")
      (value "22-05-7038-03")
      (footprint "eagle-import:7395-03")
      (libsource (lib "eagle-import") (part "22-?-0305-7038"))
    )
    (comp (ref "X20")
      (value "MSTBA4")
      (footprint "eagle-import:MSTBA4")
      (fields (field (name "MF") "FARNELL") (field (name "MPN") "1757268"))
      (libsource (lib "eagle-import") (part "MSTBA4"))
    )
    (comp (ref "X21")
      (value "MSTBA2")
      (footprint "eagle-import:MSTBA2")
      (fields (field (name "MF") "FARNELL") (field (name "MPN") "1757242"))
      (libsource (lib "eagle-import") (part "MSTBA2"))
    )
    (comp (ref "X22")
      (value "22-05-7038-03")
      (footprint "eagle-import:7395-03")
      (libsource (lib "eagle-import") (part "22-?-0305-7038"))
    )
    (comp (ref "X23")
      (value "22-05-7038-03")
      (footprint "eagle-import:7395-03")
      (libsource (lib "eagle-import") (part "22-?-0305-7038"))
    )
  )
  (nets
    (net (code "1") (name "+3V3") (class "Default")
      (node (ref "3.3V") (pin "TP") (pinfunction "TP_TP") (pintype "input"))
      (node (ref "C13") (pin "1") (pinfunction "1_1") (pintype "passive"))
      (node (ref "C14") (pin "1") (pinfunction "1_1") (pintype "passive"))
      (node (ref "C15") (pin "1") (pinfunction "1_1") (pintype "passive"))
      (node (ref "C2") (pin "1") (pinfunction "1_1") (pintype "passive"))
      (node (ref "C23") (pin "1") (pinfunction "1_1") (pintype "passive"))
      (node (ref "C30") (pin "1") (pinfunction "1_1") (pintype "passive"))
      (node (ref "C41") (pin "1") (pinfunction "1_1") (pintype "passive"))
      (node (ref "C42") (pin "1") (pinfunction "1_1") (pintype "passive"))
      (node (ref "C44") (pin "1") (pinfunction "1_1") (pintype "passive"))
      (node (ref "C5") (pin "1") (pinfunction "1_1") (pintype "passive"))
      (node (ref "C61") (pin "1") (pinfunction "1_1") (pintype "passive"))
      (node (ref "C63") (pin "1") (pinfunction "1_1") (pintype "passive"))
      (node (ref "IC1") (pin "8") (pinfunction "VCC_IO_8") (pintype "bidirectional"))
      (node (ref "IC10") (pin "5") (pinfunction "VCC_5") (pintype "power_in"))
      (node (ref "IC11") (pin "5") (pinfunction "VCC_5") (pintype "power_in"))
      (node (ref "IC12") (pin "8") (pinfunction "VCC_IO_8") (pintype "bidirectional"))
      (node (ref "IC13") (pin "5") (pinfunction "VCC_5") (pintype "power_in"))
      (node (ref "IC14") (pin "5") (pinfunction "VCC_5") (pintype "power_in"))
      (node (ref "IC15") (pin "8") (pinfunction "VCC_IO_8") (pintype "bidirectional"))
      (node (ref "IC16") (pin "5") (pinfunction "VCC_5") (pintype "power_in"))
      (node (ref "IC17") (pin "5") (pinfunction "VCC_5") (pintype "power_in"))
      (node (ref "IC2") (pin "8") (pinfunction "VCC_IO_8") (pintype "bidirectional"))
      (node (ref "IC3") (pin "5") (pinfunction "VCC_5") (pintype "power_in"))
      (node (ref "IC4") (pin "5") (pinfunction "VCC_5") (pintype "power_in"))
      (node (ref "IC5") (pin "8") (pinfunction "VCC_IO_8") (pintype "bidirectional"))
      (node (ref "IC8") (pin "5") (pinfunction "VCC_5") (pintype "power_in"))
      (node (ref "IC9") (pin "5") (pinfunction "VCC_5") (pintype "power_in"))
      (node (ref "P9") (pin "3") (pinfunction "3_3") (pintype "passive"))
      (node (ref "P9") (pin "4") (pinfunction "4_4") (pintype "passive"))
      (node (ref "R12") (pin "2") (pinfunction "2_2") (pintype "passive"))
      (node (ref "R23") (pin "2") (pinfunction "2_2") (pintype "passive"))
      (node (ref "R24") (pin "2") (pinfunction "2_2") (pintype "passive"))
      (node (ref "R26") (pin "2") (pinfunction "2_2") (pintype "passive"))
      (node (ref "R28") (pin "2") (pinfunction "2_2") (pintype "passive"))
      (node (ref "R33") (pin "2") (pinfunction "2_2") (pintype "passive"))
      (node (ref "R34") (pin "2") (pinfunction "2_2") (pintype "passive"))
      (node (ref "R36") (pin "2") (pinfunction "2_2") (pintype "passive"))
      (node (ref "R5") (pin "2") (pinfunction "2_2") (pintype "passive"))
      (node (ref "R51") (pin "2") (pinfunction "2_2") (pintype "passive"))
      (node (ref "R54") (pin "2") (pinfunction "2_2") (pintype "passive"))
      (node (ref "U1") (pin "16") (pinfunction "VCC_16") (pintype "power_in"))
      (node (ref "U18") (pin "3") (pinfunction "A2_3") (pintype "input"))
      (node (ref "U18") (pin "8") (pinfunction "VCC_8") (pintype "power_in"))
      (node (ref "U19") (pin "1") (pinfunction "VCC_1") (pintype "power_in"))
      (node (ref "U2") (pin "16") (pinfunction "VCC_16") (pintype "power_in"))
      (node (ref "U3") (pin "16") (pinfunction "VCC_16") (pintype "power_in"))
      (node (ref "U4") (pin "16") (pinfunction "VCC_16") (pintype "power_in"))
      (node (ref "U5") (pin "16") (pinfunction "VCC_16") (pintype "power_in"))
      (node (ref "X23") (pin "1") (pinfunction "S_1") (pintype "passive"))
    )
    (net (code "2") (name "+5V") (class "Default")
      (node (ref "5V") (pin "TP") (pinfunction "TP_TP") (pintype "input"))
      (node (ref "C49") (pin "1") (pinfunction "1_1") (pintype "passive"))
      (node (ref "C50") (pin "1") (pinfunction "1_1") (pintype "passive"))
      (node (ref "L1") (pin "P$2") (pinfunction "2_P$2") (pintype "passive"))
      (node (ref "P9") (pin "5") (pinfunction "5_5") (pintype "passive"))
      (node (ref "P9") (pin "6") (pinfunction "6_6") (pintype "passive"))
      (node (ref "R41") (pin "2") (pinfunction "2_2") (pintype "passive"))
      (node (ref "U6") (pin "5") (pinfunction "VFB_5") (pintype "input"))
    )
    (net (code "3") (name "/DALLAS_W1") (class "Default")
      (node (ref "P9") (pin "22") (pinfunction "22_22") (pintype "passive"))
      (node (ref "X23") (pin "2") (pinfunction "S_2") (pintype "passive"))
    )
    (net (code "4") (name "/DIR_E") (class "Default")
      (node (ref "IC12") (pin "7") (pinfunction "REFR_DIR_7") (pintype "bidirectional"))
      (node (ref "P8") (pin "15") (pinfunction "15_15") (pintype "passive"))
    )
    (net (code "5") (name "/DIR_H") (class "Default")
      (node (ref "IC15") (pin "7") (pinfunction "REFR_DIR_7") (pintype "bidirectional"))
      (node (ref "P8") (pin "16") (pinfunction "16_16") (pintype "passive"))
    )
    (net (code "6") (name "/DIR_X") (class "Default")
      (node (ref "IC1") (pin "7") (pinfunction "REFR_DIR_7") (pintype "bidirectional"))
      (node (ref "P8") (pin "26") (pinfunction "26_26") (pintype "passive"))
    )
    (net (code "7") (name "/DIR_Y") (class "Default")
      (node (ref "IC2") (pin "7") (pinfunction "REFR_DIR_7") (pintype "bidirectional"))
      (node (ref "P8") (pin "19") (pinfunction "19_19") (pintype "passive"))
    )
    (net (code "8") (name "/DIR_Z") (class "Default")
      (node (ref "IC5") (pin "7") (pinfunction "REFR_DIR_7") (pintype "bidirectional"))
      (node (ref "P8") (pin "14") (pinfunction "14_14") (pintype "passive"))
    )
    (net (code "9") (name "/ENABLE") (class "Default")
      (node (ref "IC1") (pin "22") (pinfunction "DRV_ENN_CFG6_22") (pintype "bidirectional"))
      (node (ref "IC12") (pin "22") (pinfunction "DRV_ENN_CFG6_22") (pintype "bidirectional"))
      (node (ref "IC15") (pin "22") (pinfunction "DRV_ENN_CFG6_22") (pintype "bidirectional"))
      (node (ref "IC2") (pin "22") (pinfunction "DRV_ENN_CFG6_22") (pintype "bidirectional"))
      (node (ref "IC5") (pin "22") (pinfunction "DRV_ENN_CFG6_22") (pintype "bidirectional"))
      (node (ref "P9") (pin "41") (pinfunction "41_41") (pintype "passive"))
      (node (ref "R23") (pin "1") (pinfunction "1_1") (pintype "passive"))
      (node (ref "U11") (pin "23") (pinfunction "~{OE}_23") (pintype "input"))
    )
    (net (code "10") (name "/END_STOP_X_1") (class "Default")
      (node (ref "P9") (pin "25") (pinfunction "25_25") (pintype "passive"))
      (node (ref "U19") (pin "2") (pinfunction "G=A_2") (pintype "output"))
    )
    (net (code "11") (name "/END_STOP_X_1_IN") (class "Default")
      (node (ref "U19") (pin "3") (pinfunction "A_3") (pintype "input"))
      (node (ref "X22") (pin "1") (pinfunction "S_1") (pintype "passive"))
    )
    (net (code "12") (name "/END_STOP_X_2") (class "Default")
      (node (ref "P9") (pin "11") (pinfunction "11_11") (pintype "passive"))
      (node (ref "U19") (pin "10") (pinfunction "J=D_10") (pintype "output"))
    )
    (net (code "13") (name "/END_STOP_X_2_IN") (class "Default")
      (node (ref "IC6") (pin "4") (pinfunction "O_4") (pintype "output"))
      (node (ref "U19") (pin "9") (pinfunction "D_9") (pintype "input"))
      (node (ref "X10") (pin "1") (pinfunction "S_1") (pintype "passive"))
    )
    (net (code "14") (name "/END_STOP_Y_1") (class "Default")
      (node (ref "P9") (pin "23") (pinfunction "23_23") (pintype "passive"))
      (node (ref "U19") (pin "4") (pinfunction "H=B_4") (pintype "output"))
    )
    (net (code "15") (name "/END_STOP_Y_1_IN") (class "Default")
      (node (ref "U19") (pin "5") (pinfunction "B_5") (pintype "input"))
      (node (ref "X1") (pin "1") (pinfunction "S_1") (pintype "passive"))
    )
    (net (code "16") (name "/END_STOP_Y_2") (class "Default")
      (node (ref "P9") (pin "28") (pinfunction "28_28") (pintype "passive"))
      (node (ref "U19") (pin "12") (pinfunction "K=E_12") (pintype "output"))
    )
    (net (code "17") (name "/END_STOP_Y_2_IN") (class "Default")
      (node (ref "IC7") (pin "4") (pinfunction "O_4") (pintype "output"))
      (node (ref "U19") (pin "11") (pinfunction "E_11") (pintype "input"))
      (node (ref "X19") (pin "1") (pinfunction "S_1") (pintype "passive"))
    )
    (net (code "18") (name "/END_STOP_Z_1") (class "Default")
      (node (ref "P9") (pin "13") (pinfunction "13_13") (pintype "passive"))
      (node (ref "U19") (pin "6") (pinfunction "I=C_6") (pintype "output"))
    )
    (net (code "19") (name "/END_STOP_Z_1_IN") (class "Default")
      (node (ref "U19") (pin "7") (pinfunction "C_7") (pintype "input"))
      (node (ref "X13") (pin "1") (pinfunction "S_1") (pintype "passive"))
    )
    (net (code "20") (name "/END_STOP_Z_2") (class "Default")
      (node (ref "P9") (pin "18") (pinfunction "18_18") (pintype "passive"))
      (node (ref "U19") (pin "15") (pinfunction "L=F_15") (pintype "output"))
    )
    (net (code "21") (name "/END_STOP_Z_2_IN") (class "Default")
      (node (ref "U19") (pin "14") (pinfunction "F_14") (pintype "input"))
      (node (ref "X12") (pin "1") (pinfunction "S_1") (pintype "passive"))
    )
    (net (code "22") (name "/FAN0") (class "Default")
      (node (ref "Q6") (pin "1") (pinfunction "B_1") (pintype "passive"))
      (node (ref "U11") (pin "13") (pinfunction "LED7_13") (pintype "output"))
    )
    (net (code "23") (name "/FAN1") (class "Default")
      (node (ref "Q7") (pin "1") (pinfunction "B_1") (pintype "passive"))
      (node (ref "U11") (pin "15") (pinfunction "LED8_15") (pintype "output"))
    )
    (net (code "24") (name "/FAN2") (class "Default")
      (node (ref "Q4") (pin "1") (pinfunction "B_1") (pintype "passive"))
      (node (ref "U11") (pin "16") (pinfunction "LED9_16") (pintype "output"))
    )
    (net (code "25") (name "/FAN3") (class "Default")
      (node (ref "Q5") (pin "1") (pinfunction "B_1") (pintype "passive"))
      (node (ref "U11") (pin "17") (pinfunction "LED10_17") (pintype "output"))
    )
    (net (code "26") (name "/FAULT_E") (class "Default")
      (node (ref "IC12") (pin "20") (pinfunction "SWN_DIAG0_20") (pintype "bidirectional"))
      (node (ref "P8") (pin "18") (pinfunction "18_18") (pintype "passive"))
      (node (ref "R36") (pin "1") (pinfunction "1_1") (pintype "passive"))
    )
    (net (code "27") (name "/FAULT_H") (class "Default")
      (node (ref "IC15") (pin "20") (pinfunction "SWN_DIAG0_20") (pintype "bidirectional"))
      (node (ref "P8") (pin "8") (pinfunction "8_8") (pintype "passive"))
      (node (ref "R51") (pin "1") (pinfunction "1_1") (pintype "passive"))
    )
    (net (code "28") (name "/FAULT_X") (class "Default")
      (node (ref "IC1") (pin "20") (pinfunction "SWN_DIAG0_20") (pintype "bidirectional"))
      (node (ref "P8") (pin "10") (pinfunction "10_10") (pintype "passive"))
      (node (ref "R54") (pin "1") (pinfunction "1_1") (pintype "passive"))
    )
    (net (code "29") (name "/FAULT_Y") (class "Default")
      (node (ref "IC2") (pin "20") (pinfunction "SWN_DIAG0_20") (pintype "bidirectional"))
      (node (ref "P8") (pin "9") (pinfunction "9_9") (pintype "passive"))
      (node (ref "R24") (pin "1") (pinfunction "1_1") (pintype "passive"))
    )
    (net (code "30") (name "/FAULT_Z") (class "Default")
      (node (ref "IC5") (pin "20") (pinfunction "SWN_DIAG0_20") (pintype "bidirectional"))
      (node (ref "P9") (pin "24") (pinfunction "24_24") (pintype "passive"))
      (node (ref "R28") (pin "1") (pinfunction "1_1") (pintype "passive"))
    )
    (net (code "31") (name "/HEATER_EXT1") (class "Default")
      (node (ref "Q3") (pin "4") (pinfunction "G_4") (pintype "passive"))
      (node (ref "R47") (pin "2") (pinfunction "2_2") (pintype "passive"))
      (node (ref "U11") (pin "11") (pinfunction "LED5_11") (pintype "output"))
    )
    (net (code "32") (name "/HEATER_EXT2") (class "Default")
      (node (ref "Q2") (pin "4") (pinfunction "G_4") (pintype "passive"))
      (node (ref "R48") (pin "2") (pinfunction "2_2") (pintype "passive"))
      (node (ref "U11") (pin "9") (pinfunction "LED3_9") (pintype "output"))
    )
    (net (code "33") (name "/HEATER_HBP") (class "Default")
      (node (ref "Q1") (pin "4") (pinfunction "G_4") (pintype "passive"))
      (node (ref "R46") (pin "2") (pinfunction "2_2") (pintype "passive"))
      (node (ref "U11") (pin "10") (pinfunction "LED4_10") (pintype "output"))
    )
    (net (code "34") (name "/I2C2_SCL") (class "Default")
      (node (ref "P9") (pin "19") (pinfunction "19_19") (pintype "passive"))
      (node (ref "U11") (pin "26") (pinfunction "SCL_26") (pintype "input"))
      (node (ref "U18") (pin "6") (pinfunction "SCL_6") (pintype "input"))
    )
    (net (code "35") (name "/I2C2_SDA") (class "Default")
      (node (ref "P9") (pin "20") (pinfunction "20_20") (pintype "passive"))
      (node (ref "U11") (pin "27") (pinfunction "SDA_27") (pintype "bidirectional"))
      (node (ref "U18") (pin "5") (pinfunction "SDA_5") (pintype "bidirectional"))
    )
    (net (code "36") (name "/IREF_E") (class "Default")
      (node (ref "R35") (pin "2") (pinfunction "2_2") (pintype "passive"))
      (node (ref "R61") (pin "1") (pinfunction "1_1") (pintype "passive"))
      (node (ref "R66") (pin "1") (pinfunction "1_1") (pintype "passive"))
    )
    (net (code "37") (name "/IREF_E_RAW") (class "Default")
      (node (ref "R61") (pin "2") (pinfunction "2_2") (pintype "passive"))
      (node (ref "U11") (pin "21") (pinfunction "LED14_21") (pintype "output"))
    )
    (net (code "38") (name "/IREF_H") (class "Default")
      (node (ref "R50") (pin "2") (pinfunction "2_2") (pintype "passive"))
      (node (ref "R60") (pin "1") (pinfunction "1_1") (pintype "passive"))
      (node (ref "R65") (pin "1") (pinfunction "1_1") (pintype "passive"))
    )
    (net (code "39") (name "/IREF_H_RAW") (class "Default")
      (node (ref "R60") (pin "2") (pinfunction "2_2") (pintype "passive"))
      (node (ref "U11") (pin "22") (pinfunction "LED15_22") (pintype "output"))
    )
    (net (code "40") (name "/IREF_X") (class "Default")
      (node (ref "R49") (pin "2") (pinfunction "2_2") (pintype "passive"))
      (node (ref "R64") (pin "1") (pinfunction "1_1") (pintype "passive"))
      (node (ref "R69") (pin "1") (pinfunction "1_1") (pintype "passive"))
    )
    (net (code "41") (name "/IREF_X_RAW") (class "Default")
      (node (ref "R64") (pin "2") (pinfunction "2_2") (pintype "passive"))
      (node (ref "U11") (pin "18") (pinfunction "LED11_18") (pintype "output"))
    )
    (net (code "42") (name "/IREF_Y") (class "Default")
      (node (ref "R6") (pin "2") (pinfunction "2_2") (pintype "passive"))
      (node (ref "R63") (pin "1") (pinfunction "1_1") (pintype "passive"))
      (node (ref "R68") (pin "1") (pinfunction "1_1") (pintype "passive"))
    )
    (net (code "43") (name "/IREF_Y_RAW") (class "Default")
      (node (ref "R63") (pin "2") (pinfunction "2_2") (pintype "passive"))
      (node (ref "U11") (pin "19") (pinfunction "LED12_19") (pintype "output"))
    )
    (net (code "44") (name "/IREF_Z") (class "Default")
      (node (ref "R27") (pin "2") (pinfunction "2_2") (pintype "passive"))
      (node (ref "R62") (pin "1") (pinfunction "1_1") (pintype "passive"))
      (node (ref "R67") (pin "1") (pinfunction "1_1") (pintype "passive"))
    )
    (net (code "45") (name "/IREF_Z_RAW") (class "Default")
      (node (ref "R62") (pin "2") (pinfunction "2_2") (pintype "passive"))
      (node (ref "U11") (pin "20") (pinfunction "LED13_20") (pintype "output"))
    )
    (net (code "46") (name "/SERVO_0") (class "Default")
      (node (ref "IC6") (pin "2") (pinfunction "I_2") (pintype "input"))
      (node (ref "P9") (pin "14") (pinfunction "14_14") (pintype "passive"))
    )
    (net (code "47") (name "/SERVO_0_EN") (class "Default")
      (node (ref "IC6") (pin "1") (pinfunction "OE_1") (pintype "input"))
      (node (ref "U4") (pin "15") (pinfunction "QA_15") (pintype "output"))
    )
    (net (code "48") (name "/SERVO_1") (class "Default")
      (node (ref "IC7") (pin "2") (pinfunction "I_2") (pintype "input"))
      (node (ref "P9") (pin "16") (pinfunction "16_16") (pintype "passive"))
    )
    (net (code "49") (name "/SERVO_1_EN") (class "Default")
      (node (ref "IC7") (pin "1") (pinfunction "OE_1") (pintype "input"))
      (node (ref "U3") (pin "15") (pinfunction "QA_15") (pintype "output"))
    )
    (net (code "50") (name "/SER_2") (class "Default")
      (node (ref "U1") (pin "9") (pinfunction "QH_2_9") (pintype "output"))
      (node (ref "U2") (pin "14") (pinfunction "SER_14") (pintype "input"))
    )
    (net (code "51") (name "/SER_3") (class "Default")
      (node (ref "U2") (pin "9") (pinfunction "QH_2_9") (pintype "output"))
      (node (ref "U3") (pin "14") (pinfunction "SER_14") (pintype "input"))
    )
    (net (code "52") (name "/SER_4") (class "Default")
      (node (ref "U3") (pin "9") (pinfunction "QH_2_9") (pintype "output"))
      (node (ref "U4") (pin "14") (pinfunction "SER_14") (pintype "input"))
    )
    (net (code "53") (name "/SER_5") (class "Default")
      (node (ref "U4") (pin "9") (pinfunction "QH_2_9") (pintype "output"))
      (node (ref "U5") (pin "14") (pinfunction "SER_14") (pintype "input"))
    )
    (net (code "54") (name "/SPI1_CS1") (class "Default")
      (node (ref "P9") (pin "42") (pinfunction "42_42") (pintype "passive"))
      (node (ref "U1") (pin "12") (pinfunction "RCLK_12") (pintype "input"))
      (node (ref "U2") (pin "12") (pinfunction "RCLK_12") (pintype "input"))
      (node (ref "U3") (pin "12") (pinfunction "RCLK_12") (pintype "input"))
      (node (ref "U4") (pin "12") (pinfunction "RCLK_12") (pintype "input"))
      (node (ref "U5") (pin "12") (pinfunction "RCLK_12") (pintype "input"))
    )
    (net (code "55") (name "/SPI1_MOSI") (class "Default")
      (node (ref "P9") (pin "30") (pinfunction "30_30") (pintype "passive"))
      (node (ref "U1") (pin "14") (pinfunction "SER_14") (pintype "input"))
    )
    (net (code "56") (name "/SPI1_SCLK") (class "Default")
      (node (ref "P9") (pin "31") (pinfunction "31_31") (pintype "passive"))
      (node (ref "U1") (pin "11") (pinfunction "SRCLK_11") (pintype "input"))
      (node (ref "U2") (pin "11") (pinfunction "SRCLK_11") (pintype "input"))
      (node (ref "U3") (pin "11") (pinfunction "SRCLK_11") (pintype "input"))
      (node (ref "U4") (pin "11") (pinfunction "SRCLK_11") (pintype "input"))
      (node (ref "U5") (pin "11") (pinfunction "SRCLK_11") (pintype "input"))
    )
    (net (code "57") (name "/STEP_E") (class "Default")
      (node (ref "IC12") (pin "6") (pinfunction "REFL_STEP_6") (pintype "bidirectional"))
      (node (ref "P9") (pin "12") (pinfunction "12_12") (pintype "passive"))
    )
    (net (code "58") (name "/STEP_H") (class "Default")
      (node (ref "IC15") (pin "6") (pinfunction "REFL_STEP_6") (pintype "bidirectional"))
      (node (ref "P8") (pin "11") (pinfunction "11_11") (pintype "passive"))
    )
    (net (code "59") (name "/STEP_X") (class "Default")
      (node (ref "IC1") (pin "6") (pinfunction "REFL_STEP_6") (pintype "bidirectional"))
      (node (ref "P8") (pin "17") (pinfunction "17_17") (pintype "passive"))
    )
    (net (code "60") (name "/STEP_Y") (class "Default")
      (node (ref "IC2") (pin "6") (pinfunction "REFL_STEP_6") (pintype "bidirectional"))
      (node (ref "P8") (pin "12") (pinfunction "12_12") (pintype "passive"))
    )
    (net (code "61") (name "/STEP_Z") (class "Default")
      (node (ref "IC5") (pin "6") (pinfunction "REFL_STEP_6") (pintype "bidirectional"))
      (node (ref "P8") (pin "13") (pinfunction "13_13") (pintype "passive"))
    )
    (net (code "62") (name "/SYS_5V") (class "Default")
      (node (ref "C17") (pin "1") (pinfunction "1_1") (pintype "passive"))
      (node (ref "IC6") (pin "5") (pinfunction "VCC_5") (pintype "power_in"))
      (node (ref "IC7") (pin "5") (pinfunction "VCC_5") (pintype "power_in"))
      (node (ref "P9") (pin "8") (pinfunction "8_8") (pintype "passive"))
      (node (ref "U11") (pin "1") (pinfunction "A0_1") (pintype "input"))
      (node (ref "U11") (pin "2") (pinfunction "A1_2") (pintype "input"))
      (node (ref "U11") (pin "24") (pinfunction "A5_24") (pintype "input"))
      (node (ref "U11") (pin "28") (pinfunction "VDD_28") (pintype "power_in"))
      (node (ref "U11") (pin "3") (pinfunction "A2_3") (pintype "input"))
      (node (ref "U11") (pin "4") (pinfunction "A3_4") (pintype "input"))
      (node (ref "U11") (pin "5") (pinfunction "A4_5") (pintype "input"))
      (node (ref "X1") (pin "2") (pinfunction "S_2") (pintype "passive"))
      (node (ref "X10") (pin "2") (pinfunction "S_2") (pintype "passive"))
      (node (ref "X12") (pin "2") (pinfunction "S_2") (pintype "passive"))
      (node (ref "X13") (pin "2") (pinfunction "S_2") (pintype "passive"))
      (node (ref "X19") (pin "2") (pinfunction "S_2") (pintype "passive"))
      (node (ref "X22") (pin "2") (pinfunction "S_2") (pintype "passive"))
    )
    (net (code "63") (name "/TERM_EXT1") (class "Default")
      (node (ref "C26") (pin "1") (pinfunction "1_1") (pintype "passive"))
      (node (ref "P9") (pin "33") (pinfunction "33_33") (pintype "passive"))
      (node (ref "R38") (pin "2") (pinfunction "2_2") (pintype "passive"))
    )
    (net (code "64") (name "/TERM_EXT2") (class "Default")
      (node (ref "C46") (pin "1") (pinfunction "1_1") (pintype "passive"))
      (node (ref "P9") (pin "36") (pinfunction "36_36") (pintype "passive"))
      (node (ref "R40") (pin "2") (pinfunction "2_2") (pintype "passive"))
    )
    (net (code "65") (name "/TERM_HBP") (class "Default")
      (node (ref "C45") (pin "1") (pinfunction "1_1") (pintype "passive"))
      (node (ref "P9") (pin "35") (pinfunction "35_35") (pintype "passive"))
      (node (ref "R39") (pin "2") (pinfunction "2_2") (pintype "passive"))
    )
    (net (code "66") (name "/VDD_12V") (class "Default")
      (node (ref "12V") (pin "TP") (pinfunction "TP_TP") (pintype "input"))
      (node (ref "C53") (pin "1") (pinfunction "1_1") (pintype "passive"))
      (node (ref "L2") (pin "P$1") (pinfunction "P$1_P$1") (pintype "passive"))
      (node (ref "R11") (pin "2") (pinfunction "2_2") (pintype "passive"))
      (node (ref "R19") (pin "2") (pinfunction "2_2") (pintype "passive"))
      (node (ref "R20") (pin "2") (pinfunction "2_2") (pintype "passive"))
      (node (ref "R21") (pin "2") (pinfunction "2_2") (pintype "passive"))
      (node (ref "R25") (pin "2") (pinfunction "2_2") (pintype "passive"))
      (node (ref "R42") (pin "1") (pinfunction "1_1") (pintype "passive"))
      (node (ref "X12") (pin "4") (pinfunction "S_4") (pintype "passive"))
      (node (ref "X4") (pin "1") (pinfunction "S_1") (pintype "passive"))
      (node (ref "X5") (pin "1") (pinfunction "S_1") (pintype "passive"))
      (node (ref "X6") (pin "1") (pinfunction "S_1") (pintype "passive"))
      (node (ref "X9") (pin "1") (pinfunction "S_1") (pintype "passive"))
    )
    (net (code "67") (name "/VDD_ADC") (class "Default")
      (node (ref "P9") (pin "32") (pinfunction "32_32") (pintype "passive"))
      (node (ref "R13") (pin "2") (pinfunction "2_2") (pintype "passive"))
      (node (ref "R17") (pin "2") (pinfunction "2_2") (pintype "passive"))
      (node (ref "R18") (pin "2") (pinfunction "2_2") (pintype "passive"))
    )
    (net (code "68") (name "/VDD_IN") (class "Default")
      (node (ref "12..24V") (pin "TP") (pinfunction "TP_TP") (pintype "input"))
      (node (ref "C10") (pin "1") (pinfunction "1_1") (pintype "passive"))
      (node (ref "C11") (pin "1") (pinfunction "1_1") (pintype "passive"))
      (node (ref "C16") (pin "1") (pinfunction "1_1") (pintype "passive"))
      (node (ref "C19") (pin "1") (pinfunction "1_1") (pintype "passive"))
      (node (ref "C20") (pin "2") (pinfunction "2_2") (pintype "passive"))
      (node (ref "C22") (pin "2") (pinfunction "2_2") (pintype "passive"))
      (node (ref "C24") (pin "1") (pinfunction "1_1") (pintype "passive"))
      (node (ref "C27") (pin "1") (pinfunction "1_1") (pintype "passive"))
      (node (ref "C28") (pin "2") (pinfunction "2_2") (pintype "passive"))
      (node (ref "C29") (pin "1") (pinfunction "1_1") (pintype "passive"))
      (node (ref "C31") (pin "1") (pinfunction "1_1") (pintype "passive"))
      (node (ref "C32") (pin "2") (pinfunction "2_2") (pintype "passive"))
      (node (ref "C34") (pin "1") (pinfunction "1_1") (pintype "passive"))
      (node (ref "C35") (pin "2") (pinfunction "2_2") (pintype "passive"))
      (node (ref "C38") (pin "2") (pinfunction "2_2") (pintype "passive"))
      (node (ref "C4") (pin "1") (pinfunction "1_1") (pintype "passive"))
      (node (ref "C40") (pin "1") (pinfunction "1_1") (pintype "passive"))
      (node (ref "C43") (pin "1") (pinfunction "1_1") (pintype "passive"))
      (node (ref "C47") (pin "1") (pinfunction "1_1") (pintype "passive"))
      (node (ref "C48") (pin "1") (pinfunction "1_1") (pintype "passive"))
      (node (ref "C52") (pin "1") (pinfunction "1_1") (pintype "passive"))
      (node (ref "C6") (pin "1") (pinfunction "1_1") (pintype "passive"))
      (node (ref "C60") (pin "1") (pinfunction "1_1") (pintype "passive"))
      (node (ref "C64") (pin "2") (pinfunction "2_2") (pintype "passive"))
      (node (ref "C66") (pin "2") (pinfunction "2_2") (pintype "passive"))
      (node (ref "C67") (pin "2") (pinfunction "2_2") (pintype "passive"))
      (node (ref "C69") (pin "2") (pinfunction "2_2") (pintype "passive"))
      (node (ref "C8") (pin "1") (pinfunction "1_1") (pintype "passive"))
      (node (ref "D1") (pin "C") (pinfunction "C_C") (pintype "passive"))
      (node (ref "D2") (pin "C") (pinfunction "C_C") (pintype "passive"))
      (node (ref "D3") (pin "C") (pinfunction "C_C") (pintype "passive"))
      (node (ref "D5") (pin "C") (pinfunction "C_C") (pintype "passive"))
      (node (ref "F1") (pin "P$3") (pinfunction "2_P$3") (pintype "passive"))
      (node (ref "F1") (pin "P$4") (pinfunction "2_P$4") (pintype "passive"))
      (node (ref "IC1") (pin "16") (pinfunction "VS_16") (pintype "bidirectional"))
      (node (ref "IC1") (pin "30") (pinfunction "VSA_30") (pintype "bidirectional"))
      (node (ref "IC1") (pin "31") (pinfunction "VS_31") (pintype "bidirectional"))
      (node (ref "IC12") (pin "16") (pinfunction "VS_16") (pintype "bidirectional"))
      (node (ref "IC12") (pin "30") (pinfunction "VSA_30") (pintype "bidirectional"))
      (node (ref "IC12") (pin "31") (pinfunction "VS_31") (pintype "bidirectional"))
      (node (ref "IC15") (pin "16") (pinfunction "VS_16") (pintype "bidirectional"))
      (node (ref "IC15") (pin "30") (pinfunction "VSA_30") (pintype "bidirectional"))
      (node (ref "IC15") (pin "31") (pinfunction "VS_31") (pintype "bidirectional"))
      (node (ref "IC2") (pin "16") (pinfunction "VS_16") (pintype "bidirectional"))
      (node (ref "IC2") (pin "30") (pinfunction "VSA_30") (pintype "bidirectional"))
      (node (ref "IC2") (pin "31") (pinfunction "VS_31") (pintype "bidirectional"))
      (node (ref "IC5") (pin "16") (pinfunction "VS_16") (pintype "bidirectional"))
      (node (ref "IC5") (pin "30") (pinfunction "VSA_30") (pintype "bidirectional"))
      (node (ref "IC5") (pin "31") (pinfunction "VS_31") (pintype "bidirectional"))
      (node (ref "R14") (pin "2") (pinfunction "2_2") (pintype "passive"))
      (node (ref "R15") (pin "2") (pinfunction "2_2") (pintype "passive"))
      (node (ref "R16") (pin "2") (pinfunction "2_2") (pintype "passive"))
      (node (ref "R45") (pin "1") (pinfunction "1_1") (pintype "passive"))
      (node (ref "R55") (pin "2") (pinfunction "2_2") (pintype "passive"))
      (node (ref "R56") (pin "2") (pinfunction "2_2") (pintype "passive"))
      (node (ref "R57") (pin "2") (pinfunction "2_2") (pintype "passive"))
      (node (ref "U10") (pin "4") (pinfunction "VIN_4") (pintype "power_in"))
      (node (ref "U6") (pin "11") (pinfunction "VIN_11") (pintype "power_in"))
      (node (ref "U6") (pin "2") (pinfunction "VIN_2") (pintype "power_in"))
      (node (ref "U6") (pin "3") (pinfunction "VIN_3") (pintype "power_in"))
      (node (ref "X20") (pin "1") (pinfunction "1_1") (pintype "passive"))
      (node (ref "X20") (pin "2") (pinfunction "1_2") (pintype "passive"))
      (node (ref "X21") (pin "1") (pinfunction "1_1") (pintype "passive"))
      (node (ref "X3") (pin "1") (pinfunction "1_1") (pintype "passive"))
    )
    (net (code "69") (name "/VIN") (class "Default")
      (node (ref "F1") (pin "P$1") (pinfunction "1_P$1") (pintype "passive"))
      (node (ref "F1") (pin "P$2") (pinfunction "1_P$2") (pintype "passive"))
      (node (ref "LED8") (pin "A") (pinfunction "A_A") (pintype "passive"))
      (node (ref "X2") (pin "3") (pinfunction "1_3") (pintype "passive"))
      (node (ref "X2") (pin "4") (pinfunction "1_4") (pintype "passive"))
    )
    (net (code "70") (name "GND") (class "Default")
      (node (ref "C10") (pin "2") (pinfunction "2_2") (pintype "passive"))
      (node (ref "C11") (pin "2") (pinfunction "2_2") (pintype "passive"))
      (node (ref "C12") (pin "2") (pinfunction "2_2") (pintype "passive"))
      (node (ref "C13") (pin "2") (pinfunction "2_2") (pintype "passive"))
      (node (ref "C14") (pin "2") (pinfunction "2_2") (pintype "passive"))
      (node (ref "C15") (pin "2") (pinfunction "2_2") (pintype "passive"))
      (node (ref "C16") (pin "2") (pinfunction "2_2") (pintype "passive"))
      (node (ref "C17") (pin "2") (pinfunction "2_2") (pintype "passive"))
      (node (ref "C18") (pin "2") (pinfunction "2_2") (pintype "passive"))
      (node (ref "C19") (pin "2") (pinfunction "2_2") (pintype "passive"))
      (node (ref "C2") (pin "2") (pinfunction "2_2") (pintype "passive"))
      (node (ref "C20") (pin "1") (pinfunction "1_1") (pintype "passive"))
      (node (ref "C21") (pin "1") (pinfunction "1_1") (pintype "passive"))
      (node (ref "C23") (pin "2") (pinfunction "2_2") (pintype "passive"))
      (node (ref "C24") (pin "2") (pinfunction "2_2") (pintype "passive"))
      (node (ref "C25") (pin "2") (pinfunction "2_2") (pintype "passive"))
      (node (ref "C26") (pin "2") (pinfunction "2_2") (pintype "passive"))
      (node (ref "C27") (pin "2") (pinfunction "2_2") (pintype "passive"))
      (node (ref "C28") (pin "1") (pinfunction "1_1") (pintype "passive"))
      (node (ref "C29") (pin "2") (pinfunction "2_2") (pintype "passive"))
      (node (ref "C30") (pin "2") (pinfunction "2_2") (pintype "passive"))
      (node (ref "C31") (pin "2") (pinfunction "2_2") (pintype "passive"))
      (node (ref "C32") (pin "1") (pinfunction "1_1") (pintype "passive"))
      (node (ref "C33") (pin "1") (pinfunction "1_1") (pintype "passive"))
      (node (ref "C34") (pin "2") (pinfunction "2_2") (pintype "passive"))
      (node (ref "C36") (pin "2") (pinfunction "2_2") (pintype "passive"))
      (node (ref "C37") (pin "1") (pinfunction "1_1") (pintype "passive"))
      (node (ref "C4") (pin "2") (pinfunction "2_2") (pintype "passive"))
      (node (ref "C40") (pin "2") (pinfunction "2_2") (pintype "passive"))
      (node (ref "C41") (pin "2") (pinfunction "2_2") (pintype "passive"))
      (node (ref "C42") (pin "2") (pinfunction "2_2") (pintype "passive"))
      (node (ref "C43") (pin "2") (pinfunction "2_2") (pintype "passive"))
      (node (ref "C44") (pin "2") (pinfunction "2_2") (pintype "passive"))
      (node (ref "C45") (pin "2") (pinfunction "2_2") (pintype "passive"))
      (node (ref "C46") (pin "2") (pinfunction "2_2") (pintype "passive"))
      (node (ref "C47") (pin "2") (pinfunction "2_2") (pintype "passive"))
      (node (ref "C48") (pin "2") (pinfunction "2_2") (pintype "passive"))
      (node (ref "C49") (pin "2") (pinfunction "2_2") (pintype "passive"))
      (node (ref "C5") (pin "2") (pinfunction "2_2") (pintype "passive"))
      (node (ref "C50") (pin "2") (pinfunction "2_2") (pintype "passive"))
      (node (ref "C52") (pin "2") (pinfunction "2_2") (pintype "passive"))
      (node (ref "C53") (pin "2") (pinfunction "2_2") (pintype "passive"))
      (node (ref "C54") (pin "2") (pinfunction "2_2") (pintype "passive"))
      (node (ref "C57") (pin "2") (pinfunction "2_2") (pintype "passive"))
      (node (ref "C58") (pin "2") (pinfunction "2_2") (pintype "passive"))
      (node (ref "C59") (pin "2") (pinfunction "2_2") (pintype "passive"))
      (node (ref "C6") (pin "2") (pinfunction "2_2") (pintype "passive"))
      (node (ref "C60") (pin "2") (pinfunction "2_2") (pintype "passive"))
      (node (ref "C61") (pin "2") (pinfunction "2_2") (pintype "passive"))
      (node (ref "C62") (pin "2") (pinfunction "2_2") (pintype "passive"))
      (node (ref "C63") (pin "2") (pinfunction "2_2") (pintype "passive"))
      (node (ref "C64") (pin "1") (pinfunction "1_1") (pintype "passive"))
      (node (ref "C65") (pin "1") (pinfunction "1_1") (pintype "passive"))
      (node (ref "C67") (pin "1") (pinfunction "1_1") (pintype "passive"))
      (node (ref "C68") (pin "1") (pinfunction "1_1") (pintype "passive"))
      (node (ref "C70") (pin "2") (pinfunction "2_2") (pintype "passive"))
      (node (ref "C71") (pin "2") (pinfunction "2_2") (pintype "passive"))
      (node (ref "C72") (pin "2") (pinfunction "2_2") (pintype "passive"))
      (node (ref "C73") (pin "2") (pinfunction "2_2") (pintype "passive"))
      (node (ref "C74") (pin "2") (pinfunction "2_2") (pintype "passive"))
      (node (ref "C8") (pin "2") (pinfunction "2_2") (pintype "passive"))
      (node (ref "D4") (pin "A") (pinfunction "A_A") (pintype "passive"))
      (node (ref "D5") (pin "A") (pinfunction "A_A") (pintype "passive"))
      (node (ref "IC1") (pin "1") (pinfunction "CLK_1") (pintype "bidirectional"))
      (node (ref "IC1") (pin "10") (pinfunction "SPI_MODE_10") (pintype "bidirectional"))
      (node (ref "IC1") (pin "11") (pinfunction "GND_11") (pintype "bidirectional"))
      (node (ref "IC1") (pin "12") (pinfunction "GND_12") (pintype "bidirectional"))
      (node (ref "IC1") (pin "24") (pinfunction "GNDA_24") (pintype "bidirectional"))
      (node (ref "IC1") (pin "35") (pinfunction "GND_35") (pintype "bidirectional"))
      (node (ref "IC1") (pin "36") (pinfunction "TST_MODE_36") (pintype "bidirectional"))
      (node (ref "IC1") (pin "TP") (pinfunction "GND_TP") (pintype "bidirectional"))
      (node (ref "IC10") (pin "3") (pinfunction "GND_3") (pintype "power_in"))
      (node (ref "IC11") (pin "3") (pinfunction "GND_3") (pintype "power_in"))
      (node (ref "IC12") (pin "1") (pinfunction "CLK_1") (pintype "bidirectional"))
      (node (ref "IC12") (pin "10") (pinfunction "SPI_MODE_10") (pintype "bidirectional"))
      (node (ref "IC12") (pin "11") (pinfunction "GND_11") (pintype "bidirectional"))
      (node (ref "IC12") (pin "12") (pinfunction "GND_12") (pintype "bidirectional"))
      (node (ref "IC12") (pin "24") (pinfunction "GNDA_24") (pintype "bidirectional"))
      (node (ref "IC12") (pin "35") (pinfunction "GND_35") (pintype "bidirectional"))
      (node (ref "IC12") (pin "36") (pinfunction "TST_MODE_36") (pintype "bidirectional"))
      (node (ref "IC12") (pin "TP") (pinfunction "GND_TP") (pintype "bidirectional"))
      (node (ref "IC13") (pin "3") (pinfunction "GND_3") (pintype "power_in"))
      (node (ref "IC14") (pin "3") (pinfunction "GND_3") (pintype "power_in"))
      (node (ref "IC15") (pin "1") (pinfunction "CLK_1") (pintype "bidirectional"))
      (node (ref "IC15") (pin "10") (pinfunction "SPI_MODE_10") (pintype "bidirectional"))
      (node (ref "IC15") (pin "11") (pinfunction "GND_11") (pintype "bidirectional"))
      (node (ref "IC15") (pin "12") (pinfunction "GND_12") (pintype "bidirectional"))
      (node (ref "IC15") (pin "24") (pinfunction "GNDA_24") (pintype "bidirectional"))
      (node (ref "IC15") (pin "35") (pinfunction "GND_35") (pintype "bidirectional"))
      (node (ref "IC15") (pin "36") (pinfunction "TST_MODE_36") (pintype "bidirectional"))
      (node (ref "IC15") (pin "TP") (pinfunction "GND_TP") (pintype "bidirectional"))
      (node (ref "IC16") (pin "3") (pinfunction "GND_3") (pintype "power_in"))
      (node (ref "IC17") (pin "3") (pinfunction "GND_3") (pintype "power_in"))
      (node (ref "IC2") (pin "1") (pinfunction "CLK_1") (pintype "bidirectional"))
      (node (ref "IC2") (pin "10") (pinfunction "SPI_MODE_10") (pintype "bidirectional"))
      (node (ref "IC2") (pin "11") (pinfunction "GND_11") (pintype "bidirectional"))
      (node (ref "IC2") (pin "12") (pinfunction "GND_12") (pintype "bidirectional"))
      (node (ref "IC2") (pin "24") (pinfunction "GNDA_24") (pintype "bidirectional"))
      (node (ref "IC2") (pin "35") (pinfunction "GND_35") (pintype "bidirectional"))
      (node (ref "IC2") (pin "36") (pinfunction "TST_MODE_36") (pintype "bidirectional"))
      (node (ref "IC2") (pin "TP") (pinfunction "GND_TP") (pintype "bidirectional"))
      (node (ref "IC3") (pin "3") (pinfunction "GND_3") (pintype "power_in"))
      (node (ref "IC4") (pin "3") (pinfunction "GND_3") (pintype "power_in"))
      (node (ref "IC5") (pin "1") (pinfunction "CLK_1") (pintype "bidirectional"))
      (node (ref "IC5") (pin "10") (pinfunction "SPI_MODE_10") (pintype "bidirectional"))
      (node (ref "IC5") (pin "11") (pinfunction "GND_11") (pintype "bidirectional"))
      (node (ref "IC5") (pin "12") (pinfunction "GND_12") (pintype "bidirectional"))
      (node (ref "IC5") (pin "24") (pinfunction "GNDA_24") (pintype "bidirectional"))
      (node (ref "IC5") (pin "35") (pinfunction "GND_35") (pintype "bidirectional"))
      (node (ref "IC5") (pin "36") (pinfunction "TST_MODE_36") (pintype "bidirectional"))
      (node (ref "IC5") (pin "TP") (pinfunction "GND_TP") (pintype "bidirectional"))
      (node (ref "IC6") (pin "3") (pinfunction "GND_3") (pintype "power_in"))
      (node (ref "IC7") (pin "3") (pinfunction "GND_3") (pintype "power_in"))
      (node (ref "IC8") (pin "3") (pinfunction "GND_3") (pintype "power_in"))
      (node (ref "IC9") (pin "3") (pinfunction "GND_3") (pintype "power_in"))
      (node (ref "LED4") (pin "C") (pinfunction "C_C") (pintype "passive"))
      (node (ref "P8") (pin "1") (pinfunction "1_1") (pintype "passive"))
      (node (ref "P8") (pin "2") (pinfunction "2_2") (pintype "passive"))
      (node (ref "P9") (pin "1") (pinfunction "1_1") (pintype "passive"))
      (node (ref "P9") (pin "2") (pinfunction "2_2") (pintype "passive"))
      (node (ref "P9") (pin "43") (pinfunction "43_43") (pintype "passive"))
      (node (ref "P9") (pin "44") (pinfunction "44_44") (pintype "passive"))
      (node (ref "P9") (pin "45") (pinfunction "45_45") (pintype "passive"))
      (node (ref "P9") (pin "46") (pinfunction "46_46") (pintype "passive"))
      (node (ref "Q1") (pin "1") (pinfunction "S_1") (pintype "passive"))
      (node (ref "Q1") (pin "2") (pinfunction "S_2") (pintype "passive"))
      (node (ref "Q1") (pin "3") (pinfunction "S_3") (pintype "passive"))
      (node (ref "Q2") (pin "1") (pinfunction "S_1") (pintype "passive"))
      (node (ref "Q2") (pin "2") (pinfunction "S_2") (pintype "passive"))
      (node (ref "Q2") (pin "3") (pinfunction "S_3") (pintype "passive"))
      (node (ref "Q3") (pin "1") (pinfunction "S_1") (pintype "passive"))
      (node (ref "Q3") (pin "2") (pinfunction "S_2") (pintype "passive"))
      (node (ref "Q3") (pin "3") (pinfunction "S_3") (pintype "passive"))
      (node (ref "Q4") (pin "2") (pinfunction "E_2") (pintype "passive"))
      (node (ref "Q5") (pin "2") (pinfunction "E_2") (pintype "passive"))
      (node (ref "Q6") (pin "2") (pinfunction "E_2") (pintype "passive"))
      (node (ref "Q7") (pin "2") (pinfunction "E_2") (pintype "passive"))
      (node (ref "R1") (pin "1") (pinfunction "1_1") (pintype "passive"))
      (node (ref "R10") (pin "1") (pinfunction "1_1") (pintype "passive"))
      (node (ref "R2") (pin "1") (pinfunction "1_1") (pintype "passive"))
      (node (ref "R29") (pin "1") (pinfunction "1_1") (pintype "passive"))
      (node (ref "R3") (pin "1") (pinfunction "1_1") (pintype "passive"))
      (node (ref "R30") (pin "1") (pinfunction "1_1") (pintype "passive"))
      (node (ref "R4") (pin "1") (pinfunction "1_1") (pintype "passive"))
      (node (ref "R43") (pin "2") (pinfunction "2_2") (pintype "passive"))
      (node (ref "R44") (pin "2") (pinfunction "2_2") (pintype "passive"))
      (node (ref "R46") (pin "1") (pinfunction "1_1") (pintype "passive"))
      (node (ref "R47") (pin "1") (pinfunction "1_1") (pintype "passive"))
      (node (ref "R48") (pin "1") (pinfunction "1_1") (pintype "passive"))
      (node (ref "R65") (pin "2") (pinfunction "2_2") (pintype "passive"))
      (node (ref "R66") (pin "2") (pinfunction "2_2") (pintype "passive"))
      (node (ref "R67") (pin "2") (pinfunction "2_2") (pintype "passive"))
      (node (ref "R68") (pin "2") (pinfunction "2_2") (pintype "passive"))
      (node (ref "R69") (pin "2") (pinfunction "2_2") (pintype "passive"))
      (node (ref "R7") (pin "1") (pinfunction "1_1") (pintype "passive"))
      (node (ref "R8") (pin "1") (pinfunction "1_1") (pintype "passive"))
      (node (ref "R9") (pin "1") (pinfunction "1_1") (pintype "passive"))
      (node (ref "U1") (pin "13") (pinfunction "~{OE}_13") (pintype "input"))
      (node (ref "U1") (pin "8") (pinfunction "GND_8") (pintype "passive"))
      (node (ref "U10") (pin "6") (pinfunction "GND_6") (pintype "power_in"))
      (node (ref "U10") (pin "EP") (pinfunction "EP_EP") (pintype "power_in"))
      (node (ref "U11") (pin "14") (pinfunction "VSS_14") (pintype "passive"))
      (node (ref "U18") (pin "1") (pinfunction "A0_1") (pintype "input"))
      (node (ref "U18") (pin "2") (pinfunction "A1_2") (pintype "input"))
      (node (ref "U18") (pin "4") (pinfunction "GND_4") (pintype "power_in"))
      (node (ref "U19") (pin "8") (pinfunction "VSS_8") (pintype "power_in"))
      (node (ref "U2") (pin "13") (pinfunction "~{OE}_13") (pintype "input"))
      (node (ref "U2") (pin "8") (pinfunction "GND_8") (pintype "passive"))
      (node (ref "U3") (pin "13") (pinfunction "~{OE}_13") (pintype "input"))
      (node (ref "U3") (pin "8") (pinfunction "GND_8") (pintype "passive"))
      (node (ref "U4") (pin "13") (pinfunction "~{OE}_13") (pintype "input"))
      (node (ref "U4") (pin "8") (pinfunction "GND_8") (pintype "passive"))
      (node (ref "U5") (pin "13") (pinfunction "~{OE}_13") (pintype "input"))
      (node (ref "U5") (pin "8") (pinfunction "GND_8") (pintype "passive"))
      (node (ref "U6") (pin "14") (pinfunction "PGND_14") (pintype "power_in"))
      (node (ref "U6") (pin "15") (pinfunction "PGND_15") (pintype "power_in"))
      (node (ref "U6") (pin "4") (pinfunction "SGND_4") (pintype "power_in"))
      (node (ref "U6") (pin "P$17") (pinfunction "EP_P$17") (pintype "power_in"))
      (node (ref "X1") (pin "3") (pinfunction "S_3") (pintype "passive"))
      (node (ref "X10") (pin "3") (pinfunction "S_3") (pintype "passive"))
      (node (ref "X11") (pin "1") (pinfunction "S_1") (pintype "passive"))
      (node (ref "X12") (pin "3") (pinfunction "S_3") (pintype "passive"))
      (node (ref "X13") (pin "3") (pinfunction "S_3") (pintype "passive"))
      (node (ref "X19") (pin "3") (pinfunction "S_3") (pintype "passive"))
      (node (ref "X2") (pin "1") (pinfunction "1_1") (pintype "passive"))
      (node (ref "X2") (pin "2") (pinfunction "1_2") (pintype "passive"))
      (node (ref "X22") (pin "3") (pinfunction "S_3") (pintype "passive"))
      (node (ref "X23") (pin "3") (pinfunction "S_3") (pintype "passive"))
      (node (ref "X7") (pin "1") (pinfunction "S_1") (pintype "passive"))
      (node (ref "X8") (pin "1") (pinfunction "S_1") (pintype "passive"))
    )
    (net (code "71") (name "Net-(C51-Pad1)") (class "Default")
      (node (ref "C51") (pin "1") (pinfunction "1_1") (pintype "passive"))
      (node (ref "R58") (pin "1") (pinfunction "1_1") (pintype "passive"))
    )
    (net (code "72") (name "Net-(C56-Pad2)") (class "Default")
      (node (ref "C56") (pin "2") (pinfunction "2_2") (pintype "passive"))
      (node (ref "R44") (pin "1") (pinfunction "1_1") (pintype "passive"))
    )
    (net (code "73") (name "Net-(IC1-5VOUT)") (class "Default")
      (node (ref "C21") (pin "2") (pinfunction "2_2") (pintype "passive"))
      (node (ref "IC1") (pin "25") (pinfunction "5VOUT_25") (pintype "bidirectional"))
      (node (ref "R53") (pin "1") (pinfunction "1_1") (pintype "passive"))
    )
    (net (code "74") (name "Net-(IC1-AIN_IREF)") (class "Default")
      (node (ref "C12") (pin "1") (pinfunction "1_1") (pintype "passive"))
      (node (ref "IC1") (pin "23") (pinfunction "AIN_IREF_23") (pintype "bidirectional"))
      (node (ref "R49") (pin "1") (pinfunction "1_1") (pintype "passive"))
    )
    (net (code "75") (name "Net-(IC1-BRA)") (class "Default")
      (node (ref "IC1") (pin "33") (pinfunction "BRA_33") (pintype "bidirectional"))
      (node (ref "R2") (pin "2") (pinfunction "2_2") (pintype "passive"))
    )
    (net (code "76") (name "Net-(IC1-BRB)") (class "Default")
      (node (ref "IC1") (pin "14") (pinfunction "BRB_14") (pintype "bidirectional"))
      (node (ref "R1") (pin "2") (pinfunction "2_2") (pintype "passive"))
    )
    (net (code "77") (name "Net-(IC1-CPI)") (class "Default")
      (node (ref "C1") (pin "1") (pinfunction "1_1") (pintype "passive"))
      (node (ref "IC1") (pin "28") (pinfunction "CPI_28") (pintype "bidirectional"))
    )
    (net (code "78") (name "Net-(IC1-CPO)") (class "Default")
      (node (ref "C1") (pin "2") (pinfunction "2_2") (pintype "passive"))
      (node (ref "IC1") (pin "27") (pinfunction "CPO_27") (pintype "bidirectional"))
    )
    (net (code "79") (name "Net-(IC1-ENCA_DCIN_CFG5)") (class "Default")
      (node (ref "IC1") (pin "19") (pinfunction "ENCA_DCIN_CFG5_19") (pintype "bidirectional"))
      (node (ref "U1") (pin "1") (pinfunction "QB_1") (pintype "output"))
    )
    (net (code "80") (name "Net-(IC1-ENCB_DCEN_CFG4)") (class "Default")
      (node (ref "IC1") (pin "18") (pinfunction "ENCB_DCEN_CFG4_18") (pintype "bidirectional"))
      (node (ref "U1") (pin "2") (pinfunction "QC_2") (pintype "output"))
    )
    (net (code "81") (name "Net-(IC1-OA1)") (class "Default")
      (node (ref "IC1") (pin "34") (pinfunction "OA1_34") (pintype "bidirectional"))
      (node (ref "X14") (pin "2") (pinfunction "S_2") (pintype "passive"))
    )
    (net (code "82") (name "Net-(IC1-OA2)") (class "Default")
      (node (ref "IC1") (pin "32") (pinfunction "OA2_32") (pintype "bidirectional"))
      (node (ref "X14") (pin "3") (pinfunction "S_3") (pintype "passive"))
    )
    (net (code "83") (name "Net-(IC1-OB1)") (class "Default")
      (node (ref "IC1") (pin "13") (pinfunction "OB1_13") (pintype "bidirectional"))
      (node (ref "X14") (pin "1") (pinfunction "S_1") (pintype "passive"))
    )
    (net (code "84") (name "Net-(IC1-OB2)") (class "Default")
      (node (ref "IC1") (pin "15") (pinfunction "OB2_15") (pintype "bidirectional"))
      (node (ref "X14") (pin "4") (pinfunction "S_4") (pintype "passive"))
    )
    (net (code "85") (name "Net-(IC1-SCK_CFG2)") (class "Default")
      (node (ref "IC1") (pin "3") (pinfunction "SCK_CFG2_3") (pintype "bidirectional"))
      (node (ref "IC3") (pin "4") (pinfunction "O_4") (pintype "output"))
    )
    (net (code "86") (name "Net-(IC1-SDI_NAI_CFG1)") (class "Default")
      (node (ref "IC1") (pin "4") (pinfunction "SDI_NAI_CFG1_4") (pintype "bidirectional"))
      (node (ref "IC4") (pin "4") (pinfunction "O_4") (pintype "output"))
    )
    (net (code "87") (name "Net-(IC1-SDO_NAO_CFG0)") (class "Default")
      (node (ref "IC1") (pin "5") (pinfunction "SDO_NAO_CFG0_5") (pintype "bidirectional"))
      (node (ref "U1") (pin "3") (pinfunction "QD_3") (pintype "output"))
    )
    (net (code "88") (name "Net-(IC1-VCC)") (class "Default")
      (node (ref "C71") (pin "1") (pinfunction "1_1") (pintype "passive"))
      (node (ref "IC1") (pin "26") (pinfunction "VCC_26") (pintype "bidirectional"))
      (node (ref "R53") (pin "2") (pinfunction "2_2") (pintype "passive"))
    )
    (net (code "89") (name "Net-(IC1-VCP)") (class "Default")
      (node (ref "C22") (pin "1") (pinfunction "1_1") (pintype "passive"))
      (node (ref "IC1") (pin "29") (pinfunction "VCP_29") (pintype "bidirectional"))
    )
    (net (code "90") (name "Net-(IC2-5VOUT)") (class "Default")
      (node (ref "C33") (pin "2") (pinfunction "2_2") (pintype "passive"))
      (node (ref "IC2") (pin "25") (pinfunction "5VOUT_25") (pintype "bidirectional"))
      (node (ref "R59") (pin "1") (pinfunction "1_1") (pintype "passive"))
    )
    (net (code "91") (name "Net-(IC2-AIN_IREF)") (class "Default")
      (node (ref "C18") (pin "1") (pinfunction "1_1") (pintype "passive"))
      (node (ref "IC2") (pin "23") (pinfunction "AIN_IREF_23") (pintype "bidirectional"))
      (node (ref "R6") (pin "1") (pinfunction "1_1") (pintype "passive"))
    )
    (net (code "92") (name "Net-(IC2-BRA)") (class "Default")
      (node (ref "IC2") (pin "33") (pinfunction "BRA_33") (pintype "bidirectional"))
      (node (ref "R4") (pin "2") (pinfunction "2_2") (pintype "passive"))
    )
    (net (code "93") (name "Net-(IC2-BRB)") (class "Default")
      (node (ref "IC2") (pin "14") (pinfunction "BRB_14") (pintype "bidirectional"))
      (node (ref "R3") (pin "2") (pinfunction "2_2") (pintype "passive"))
    )
    (net (code "94") (name "Net-(IC2-CPI)") (class "Default")
      (node (ref "C3") (pin "1") (pinfunction "1_1") (pintype "passive"))
      (node (ref "IC2") (pin "28") (pinfunction "CPI_28") (pintype "bidirectional"))
    )
    (net (code "95") (name "Net-(IC2-CPO)") (class "Default")
      (node (ref "C3") (pin "2") (pinfunction "2_2") (pintype "passive"))
      (node (ref "IC2") (pin "27") (pinfunction "CPO_27") (pintype "bidirectional"))
    )
    (net (code "96") (name "Net-(IC2-ENCA_DCIN_CFG5)") (class "Default")
      (node (ref "IC2") (pin "19") (pinfunction "ENCA_DCIN_CFG5_19") (pintype "bidirectional"))
      (node (ref "U2") (pin "1") (pinfunction "QB_1") (pintype "output"))
    )
    (net (code "97") (name "Net-(IC2-ENCB_DCEN_CFG4)") (class "Default")
      (node (ref "IC2") (pin "18") (pinfunction "ENCB_DCEN_CFG4_18") (pintype "bidirectional"))
      (node (ref "U2") (pin "2") (pinfunction "QC_2") (pintype "output"))
    )
    (net (code "98") (name "Net-(IC2-OA1)") (class "Default")
      (node (ref "IC2") (pin "34") (pinfunction "OA1_34") (pintype "bidirectional"))
      (node (ref "X15") (pin "2") (pinfunction "S_2") (pintype "passive"))
    )
    (net (code "99") (name "Net-(IC2-OA2)") (class "Default")
      (node (ref "IC2") (pin "32") (pinfunction "OA2_32") (pintype "bidirectional"))
      (node (ref "X15") (pin "3") (pinfunction "S_3") (pintype "passive"))
    )
    (net (code "100") (name "Net-(IC2-OB1)") (class "Default")
      (node (ref "IC2") (pin "13") (pinfunction "OB1_13") (pintype "bidirectional"))
      (node (ref "X15") (pin "1") (pinfunction "S_1") (pintype "passive"))
    )
    (net (code "101") (name "Net-(IC2-OB2)") (class "Default")
      (node (ref "IC2") (pin "15") (pinfunction "OB2_15") (pintype "bidirectional"))
      (node (ref "X15") (pin "4") (pinfunction "S_4") (pintype "passive"))
    )
    (net (code "102") (name "Net-(IC2-SCK_CFG2)") (class "Default")
      (node (ref "IC2") (pin "3") (pinfunction "SCK_CFG2_3") (pintype "bidirectional"))
      (node (ref "IC8") (pin "4") (pinfunction "O_4") (pintype "output"))
    )
    (net (code "103") (name "Net-(IC2-SDI_NAI_CFG1)") (class "Default")
      (node (ref "IC2") (pin "4") (pinfunction "SDI_NAI_CFG1_4") (pintype "bidirectional"))
      (node (ref "IC9") (pin "4") (pinfunction "O_4") (pintype "output"))
    )
    (net (code "104") (name "Net-(IC2-SDO_NAO_CFG0)") (class "Default")
      (node (ref "IC2") (pin "5") (pinfunction "SDO_NAO_CFG0_5") (pintype "bidirectional"))
      (node (ref "U2") (pin "3") (pinfunction "QD_3") (pintype "output"))
    )
    (net (code "105") (name "Net-(IC2-VCC)") (class "Default")
      (node (ref "C72") (pin "1") (pinfunction "1_1") (pintype "passive"))
      (node (ref "IC2") (pin "26") (pinfunction "VCC_26") (pintype "bidirectional"))
      (node (ref "R59") (pin "2") (pinfunction "2_2") (pintype "passive"))
    )
    (net (code "106") (name "Net-(IC2-VCP)") (class "Default")
      (node (ref "C35") (pin "1") (pinfunction "1_1") (pintype "passive"))
      (node (ref "IC2") (pin "29") (pinfunction "VCP_29") (pintype "bidirectional"))
    )
    (net (code "107") (name "Net-(IC3A-I)") (class "Default")
      (node (ref "IC3") (pin "2") (pinfunction "I_2") (pintype "input"))
      (node (ref "U1") (pin "4") (pinfunction "QE_4") (pintype "output"))
    )
    (net (code "108") (name "Net-(IC3A-OE)") (class "Default")
      (node (ref "IC3") (pin "1") (pinfunction "OE_1") (pintype "input"))
      (node (ref "U1") (pin "5") (pinfunction "QF_5") (pintype "output"))
    )
    (net (code "109") (name "Net-(IC4A-I)") (class "Default")
      (node (ref "IC4") (pin "2") (pinfunction "I_2") (pintype "input"))
      (node (ref "U1") (pin "6") (pinfunction "QG_6") (pintype "output"))
    )
    (net (code "110") (name "Net-(IC4A-OE)") (class "Default")
      (node (ref "IC4") (pin "1") (pinfunction "OE_1") (pintype "input"))
      (node (ref "U1") (pin "7") (pinfunction "QH_7") (pintype "output"))
    )
    (net (code "111") (name "Net-(IC5-5VOUT)") (class "Default")
      (node (ref "C37") (pin "2") (pinfunction "2_2") (pintype "passive"))
      (node (ref "IC5") (pin "25") (pinfunction "5VOUT_25") (pintype "bidirectional"))
      (node (ref "R70") (pin "1") (pinfunction "1_1") (pintype "passive"))
    )
    (net (code "112") (name "Net-(IC5-AIN_IREF)") (class "Default")
      (node (ref "C25") (pin "1") (pinfunction "1_1") (pintype "passive"))
      (node (ref "IC5") (pin "23") (pinfunction "AIN_IREF_23") (pintype "bidirectional"))
      (node (ref "R27") (pin "1") (pinfunction "1_1") (pintype "passive"))
    )
    (net (code "113") (name "Net-(IC5-BRA)") (class "Default")
      (node (ref "IC5") (pin "33") (pinfunction "BRA_33") (pintype "bidirectional"))
      (node (ref "R8") (pin "2") (pinfunction "2_2") (pintype "passive"))
    )
    (net (code "114") (name "Net-(IC5-BRB)") (class "Default")
      (node (ref "IC5") (pin "14") (pinfunction "BRB_14") (pintype "bidirectional"))
      (node (ref "R7") (pin "2") (pinfunction "2_2") (pintype "passive"))
    )
    (net (code "115") (name "Net-(IC5-CPI)") (class "Default")
      (node (ref "C7") (pin "1") (pinfunction "1_1") (pintype "passive"))
      (node (ref "IC5") (pin "28") (pinfunction "CPI_28") (pintype "bidirectional"))
    )
    (net (code "116") (name "Net-(IC5-CPO)") (class "Default")
      (node (ref "C7") (pin "2") (pinfunction "2_2") (pintype "passive"))
      (node (ref "IC5") (pin "27") (pinfunction "CPO_27") (pintype "bidirectional"))
    )
    (net (code "117") (name "Net-(IC5-ENCA_DCIN_CFG5)") (class "Default")
      (node (ref "IC5") (pin "19") (pinfunction "ENCA_DCIN_CFG5_19") (pintype "bidirectional"))
      (node (ref "U3") (pin "1") (pinfunction "QB_1") (pintype "output"))
    )
    (net (code "118") (name "Net-(IC5-ENCB_DCEN_CFG4)") (class "Default")
      (node (ref "IC5") (pin "18") (pinfunction "ENCB_DCEN_CFG4_18") (pintype "bidirectional"))
      (node (ref "U3") (pin "2") (pinfunction "QC_2") (pintype "output"))
    )
    (net (code "119") (name "Net-(IC5-OA1)") (class "Default")
      (node (ref "IC5") (pin "34") (pinfunction "OA1_34") (pintype "bidirectional"))
      (node (ref "X16") (pin "2") (pinfunction "S_2") (pintype "passive"))
    )
    (net (code "120") (name "Net-(IC5-OA2)") (class "Default")
      (node (ref "IC5") (pin "32") (pinfunction "OA2_32") (pintype "bidirectional"))
      (node (ref "X16") (pin "3") (pinfunction "S_3") (pintype "passive"))
    )
    (net (code "121") (name "Net-(IC5-OB1)") (class "Default")
      (node (ref "IC5") (pin "13") (pinfunction "OB1_13") (pintype "bidirectional"))
      (node (ref "X16") (pin "1") (pinfunction "S_1") (pintype "passive"))
    )
    (net (code "122") (name "Net-(IC5-OB2)") (class "Default")
      (node (ref "IC5") (pin "15") (pinfunction "OB2_15") (pintype "bidirectional"))
      (node (ref "X16") (pin "4") (pinfunction "S_4") (pintype "passive"))
    )
    (net (code "123") (name "Net-(IC5-SDO_NAO_CFG0)") (class "Default")
      (node (ref "IC5") (pin "5") (pinfunction "SDO_NAO_CFG0_5") (pintype "bidirectional"))
      (node (ref "U3") (pin "3") (pinfunction "QD_3") (pintype "output"))
    )
    (net (code "124") (name "Net-(IC5-VCC)") (class "Default")
      (node (ref "C73") (pin "1") (pinfunction "1_1") (pintype "passive"))
      (node (ref "IC5") (pin "26") (pinfunction "VCC_26") (pintype "bidirectional"))
      (node (ref "R70") (pin "2") (pinfunction "2_2") (pintype "passive"))
    )
    (net (code "125") (name "Net-(IC5-VCP)") (class "Default")
      (node (ref "C38") (pin "1") (pinfunction "1_1") (pintype "passive"))
      (node (ref "IC5") (pin "29") (pinfunction "VCP_29") (pintype "bidirectional"))
    )
    (net (code "126") (name "Net-(IC8A-I)") (class "Default")
      (node (ref "IC8") (pin "2") (pinfunction "I_2") (pintype "input"))
      (node (ref "U2") (pin "4") (pinfunction "QE_4") (pintype "output"))
    )
    (net (code "127") (name "Net-(IC8A-OE)") (class "Default")
      (node (ref "IC8") (pin "1") (pinfunction "OE_1") (pintype "input"))
      (node (ref "U2") (pin "5") (pinfunction "QF_5") (pintype "output"))
    )
    (net (code "128") (name "Net-(IC9A-I)") (class "Default")
      (node (ref "IC9") (pin "2") (pinfunction "I_2") (pintype "input"))
      (node (ref "U2") (pin "6") (pinfunction "QG_6") (pintype "output"))
    )
    (net (code "129") (name "Net-(IC9A-OE)") (class "Default")
      (node (ref "IC9") (pin "1") (pinfunction "OE_1") (pintype "input"))
      (node (ref "U2") (pin "7") (pinfunction "QH_7") (pintype "output"))
    )
    (net (code "130") (name "Net-(IC10A-I)") (class "Default")
      (node (ref "IC10") (pin "2") (pinfunction "I_2") (pintype "input"))
      (node (ref "U3") (pin "4") (pinfunction "QE_4") (pintype "output"))
    )
    (net (code "131") (name "Net-(IC10A-O)") (class "Default")
      (node (ref "IC10") (pin "4") (pinfunction "O_4") (pintype "output"))
      (node (ref "IC5") (pin "3") (pinfunction "SCK_CFG2_3") (pintype "bidirectional"))
    )
    (net (code "132") (name "Net-(IC10A-OE)") (class "Default")
      (node (ref "IC10") (pin "1") (pinfunction "OE_1") (pintype "input"))
      (node (ref "U3") (pin "5") (pinfunction "QF_5") (pintype "output"))
    )
    (net (code "133") (name "Net-(IC11A-I)") (class "Default")
      (node (ref "IC11") (pin "2") (pinfunction "I_2") (pintype "input"))
      (node (ref "U3") (pin "6") (pinfunction "QG_6") (pintype "output"))
    )
    (net (code "134") (name "Net-(IC11A-O)") (class "Default")
      (node (ref "IC11") (pin "4") (pinfunction "O_4") (pintype "output"))
      (node (ref "IC5") (pin "4") (pinfunction "SDI_NAI_CFG1_4") (pintype "bidirectional"))
    )
    (net (code "135") (name "Net-(IC11A-OE)") (class "Default")
      (node (ref "IC11") (pin "1") (pinfunction "OE_1") (pintype "input"))
      (node (ref "U3") (pin "7") (pinfunction "QH_7") (pintype "output"))
    )
    (net (code "136") (name "Net-(IC12-5VOUT)") (class "Default")
      (node (ref "C65") (pin "2") (pinfunction "2_2") (pintype "passive"))
      (node (ref "IC12") (pin "25") (pinfunction "5VOUT_25") (pintype "bidirectional"))
      (node (ref "R71") (pin "1") (pinfunction "1_1") (pintype "passive"))
    )
    (net (code "137") (name "Net-(IC12-AIN_IREF)") (class "Default")
      (node (ref "C62") (pin "1") (pinfunction "1_1") (pintype "passive"))
      (node (ref "IC12") (pin "23") (pinfunction "AIN_IREF_23") (pintype "bidirectional"))
      (node (ref "R35") (pin "1") (pinfunction "1_1") (pintype "passive"))
    )
    (net (code "138") (name "Net-(IC12-BRA)") (class "Default")
      (node (ref "IC12") (pin "33") (pinfunction "BRA_33") (pintype "bidirectional"))
      (node (ref "R30") (pin "2") (pinfunction "2_2") (pintype "passive"))
    )
    (net (code "139") (name "Net-(IC12-BRB)") (class "Default")
      (node (ref "IC12") (pin "14") (pinfunction "BRB_14") (pintype "bidirectional"))
      (node (ref "R29") (pin "2") (pinfunction "2_2") (pintype "passive"))
    )
    (net (code "140") (name "Net-(IC12-CPI)") (class "Default")
      (node (ref "C39") (pin "1") (pinfunction "1_1") (pintype "passive"))
      (node (ref "IC12") (pin "28") (pinfunction "CPI_28") (pintype "bidirectional"))
    )
    (net (code "141") (name "Net-(IC12-CPO)") (class "Default")
      (node (ref "C39") (pin "2") (pinfunction "2_2") (pintype "passive"))
      (node (ref "IC12") (pin "27") (pinfunction "CPO_27") (pintype "bidirectional"))
    )
    (net (code "142") (name "Net-(IC12-ENCA_DCIN_CFG5)") (class "Default")
      (node (ref "IC12") (pin "19") (pinfunction "ENCA_DCIN_CFG5_19") (pintype "bidirectional"))
      (node (ref "U4") (pin "1") (pinfunction "QB_1") (pintype "output"))
    )
    (net (code "143") (name "Net-(IC12-ENCB_DCEN_CFG4)") (class "Default")
      (node (ref "IC12") (pin "18") (pinfunction "ENCB_DCEN_CFG4_18") (pintype "bidirectional"))
      (node (ref "U4") (pin "2") (pinfunction "QC_2") (pintype "output"))
    )
    (net (code "144") (name "Net-(IC12-OA1)") (class "Default")
      (node (ref "IC12") (pin "34") (pinfunction "OA1_34") (pintype "bidirectional"))
      (node (ref "X17") (pin "2") (pinfunction "S_2") (pintype "passive"))
    )
    (net (code "145") (name "Net-(IC12-OA2)") (class "Default")
      (node (ref "IC12") (pin "32") (pinfunction "OA2_32") (pintype "bidirectional"))
      (node (ref "X17") (pin "3") (pinfunction "S_3") (pintype "passive"))
    )
    (net (code "146") (name "Net-(IC12-OB1)") (class "Default")
      (node (ref "IC12") (pin "13") (pinfunction "OB1_13") (pintype "bidirectional"))
      (node (ref "X17") (pin "1") (pinfunction "S_1") (pintype "passive"))
    )
    (net (code "147") (name "Net-(IC12-OB2)") (class "Default")
      (node (ref "IC12") (pin "15") (pinfunction "OB2_15") (pintype "bidirectional"))
      (node (ref "X17") (pin "4") (pinfunction "S_4") (pintype "passive"))
    )
    (net (code "148") (name "Net-(IC12-SCK_CFG2)") (class "Default")
      (node (ref "IC12") (pin "3") (pinfunction "SCK_CFG2_3") (pintype "bidirectional"))
      (node (ref "IC13") (pin "4") (pinfunction "O_4") (pintype "output"))
    )
    (net (code "149") (name "Net-(IC12-SDI_NAI_CFG1)") (class "Default")
      (node (ref "IC12") (pin "4") (pinfunction "SDI_NAI_CFG1_4") (pintype "bidirectional"))
      (node (ref "IC14") (pin "4") (pinfunction "O_4") (pintype "output"))
    )
    (net (code "150") (name "Net-(IC12-SDO_NAO_CFG0)") (class "Default")
      (node (ref "IC12") (pin "5") (pinfunction "SDO_NAO_CFG0_5") (pintype "bidirectional"))
      (node (ref "U4") (pin "3") (pinfunction "QD_3") (pintype "output"))
    )
    (net (code "151") (name "Net-(IC12-VCC)") (class "Default")
      (node (ref "C74") (pin "1") (pinfunction "1_1") (pintype "passive"))
      (node (ref "IC12") (pin "26") (pinfunction "VCC_26") (pintype "bidirectional"))
      (node (ref "R71") (pin "2") (pinfunction "2_2") (pintype "passive"))
    )
    (net (code "152") (name "Net-(IC12-VCP)") (class "Default")
      (node (ref "C66") (pin "1") (pinfunction "1_1") (pintype "passive"))
      (node (ref "IC12") (pin "29") (pinfunction "VCP_29") (pintype "bidirectional"))
    )
    (net (code "153") (name "Net-(IC13A-I)") (class "Default")
      (node (ref "IC13") (pin "2") (pinfunction "I_2") (pintype "input"))
      (node (ref "U4") (pin "4") (pinfunction "QE_4") (pintype "output"))
    )
    (net (code "154") (name "Net-(IC13A-OE)") (class "Default")
      (node (ref "IC13") (pin "1") (pinfunction "OE_1") (pintype "input"))
      (node (ref "U4") (pin "5") (pinfunction "QF_5") (pintype "output"))
    )
    (net (code "155") (name "Net-(IC14A-I)") (class "Default")
      (node (ref "IC14") (pin "2") (pinfunction "I_2") (pintype "input"))
      (node (ref "U4") (pin "6") (pinfunction "QG_6") (pintype "output"))
    )
    (net (code "156") (name "Net-(IC14A-OE)") (class "Default")
      (node (ref "IC14") (pin "1") (pinfunction "OE_1") (pintype "input"))
      (node (ref "U4") (pin "7") (pinfunction "QH_7") (pintype "output"))
    )
    (net (code "157") (name "Net-(IC15-5VOUT)") (class "Default")
      (node (ref "C68") (pin "2") (pinfunction "2_2") (pintype "passive"))
      (node (ref "IC15") (pin "25") (pinfunction "5VOUT_25") (pintype "bidirectional"))
      (node (ref "R52") (pin "1") (pinfunction "1_1") (pintype "passive"))
    )
    (net (code "158") (name "Net-(IC15-AIN_IREF)") (class "Default")
      (node (ref "C36") (pin "1") (pinfunction "1_1") (pintype "passive"))
      (node (ref "IC15") (pin "23") (pinfunction "AIN_IREF_23") (pintype "bidirectional"))
      (node (ref "R50") (pin "1") (pinfunction "1_1") (pintype "passive"))
    )
    (net (code "159") (name "Net-(IC15-BRA)") (class "Default")
      (node (ref "IC15") (pin "33") (pinfunction "BRA_33") (pintype "bidirectional"))
      (node (ref "R10") (pin "2") (pinfunction "2_2") (pintype "passive"))
    )
    (net (code "160") (name "Net-(IC15-BRB)") (class "Default")
      (node (ref "IC15") (pin "14") (pinfunction "BRB_14") (pintype "bidirectional"))
      (node (ref "R9") (pin "2") (pinfunction "2_2") (pintype "passive"))
    )
    (net (code "161") (name "Net-(IC15-CPI)") (class "Default")
      (node (ref "C9") (pin "1") (pinfunction "1_1") (pintype "passive"))
      (node (ref "IC15") (pin "28") (pinfunction "CPI_28") (pintype "bidirectional"))
    )
    (net (code "162") (name "Net-(IC15-CPO)") (class "Default")
      (node (ref "C9") (pin "2") (pinfunction "2_2") (pintype "passive"))
      (node (ref "IC15") (pin "27") (pinfunction "CPO_27") (pintype "bidirectional"))
    )
    (net (code "163") (name "Net-(IC15-ENCA_DCIN_CFG5)") (class "Default")
      (node (ref "IC15") (pin "19") (pinfunction "ENCA_DCIN_CFG5_19") (pintype "bidirectional"))
      (node (ref "U5") (pin "1") (pinfunction "QB_1") (pintype "output"))
    )
    (net (code "164") (name "Net-(IC15-ENCB_DCEN_CFG4)") (class "Default")
      (node (ref "IC15") (pin "18") (pinfunction "ENCB_DCEN_CFG4_18") (pintype "bidirectional"))
      (node (ref "U5") (pin "2") (pinfunction "QC_2") (pintype "output"))
    )
    (net (code "165") (name "Net-(IC15-OA1)") (class "Default")
      (node (ref "IC15") (pin "34") (pinfunction "OA1_34") (pintype "bidirectional"))
      (node (ref "X18") (pin "2") (pinfunction "S_2") (pintype "passive"))
    )
    (net (code "166") (name "Net-(IC15-OA2)") (class "Default")
      (node (ref "IC15") (pin "32") (pinfunction "OA2_32") (pintype "bidirectional"))
      (node (ref "X18") (pin "3") (pinfunction "S_3") (pintype "passive"))
    )
    (net (code "167") (name "Net-(IC15-OB1)") (class "Default")
      (node (ref "IC15") (pin "13") (pinfunction "OB1_13") (pintype "bidirectional"))
      (node (ref "X18") (pin "1") (pinfunction "S_1") (pintype "passive"))
    )
    (net (code "168") (name "Net-(IC15-OB2)") (class "Default")
      (node (ref "IC15") (pin "15") (pinfunction "OB2_15") (pintype "bidirectional"))
      (node (ref "X18") (pin "4") (pinfunction "S_4") (pintype "passive"))
    )
    (net (code "169") (name "Net-(IC15-SCK_CFG2)") (class "Default")
      (node (ref "IC15") (pin "3") (pinfunction "SCK_CFG2_3") (pintype "bidirectional"))
      (node (ref "IC16") (pin "4") (pinfunction "O_4") (pintype "output"))
    )
    (net (code "170") (name "Net-(IC15-SDI_NAI_CFG1)") (class "Default")
      (node (ref "IC15") (pin "4") (pinfunction "SDI_NAI_CFG1_4") (pintype "bidirectional"))
      (node (ref "IC17") (pin "4") (pinfunction "O_4") (pintype "output"))
    )
    (net (code "171") (name "Net-(IC15-SDO_NAO_CFG0)") (class "Default")
      (node (ref "IC15") (pin "5") (pinfunction "SDO_NAO_CFG0_5") (pintype "bidirectional"))
      (node (ref "U5") (pin "3") (pinfunction "QD_3") (pintype "output"))
    )
    (net (code "172") (name "Net-(IC15-VCC)") (class "Default")
      (node (ref "C70") (pin "1") (pinfunction "1_1") (pintype "passive"))
      (node (ref "IC15") (pin "26") (pinfunction "VCC_26") (pintype "bidirectional"))
      (node (ref "R52") (pin "2") (pinfunction "2_2") (pintype "passive"))
    )
    (net (code "173") (name "Net-(IC15-VCP)") (class "Default")
      (node (ref "C69") (pin "1") (pinfunction "1_1") (pintype "passive"))
      (node (ref "IC15") (pin "29") (pinfunction "VCP_29") (pintype "bidirectional"))
    )
    (net (code "174") (name "Net-(IC16A-I)") (class "Default")
      (node (ref "IC16") (pin "2") (pinfunction "I_2") (pintype "input"))
      (node (ref "U5") (pin "4") (pinfunction "QE_4") (pintype "output"))
    )
    (net (code "175") (name "Net-(IC16A-OE)") (class "Default")
      (node (ref "IC16") (pin "1") (pinfunction "OE_1") (pintype "input"))
      (node (ref "U5") (pin "5") (pinfunction "QF_5") (pintype "output"))
    )
    (net (code "176") (name "Net-(IC17A-I)") (class "Default")
      (node (ref "IC17") (pin "2") (pinfunction "I_2") (pintype "input"))
      (node (ref "U5") (pin "6") (pinfunction "QG_6") (pintype "output"))
    )
    (net (code "177") (name "Net-(IC17A-OE)") (class "Default")
      (node (ref "IC17") (pin "1") (pinfunction "OE_1") (pintype "input"))
      (node (ref "U5") (pin "7") (pinfunction "QH_7") (pintype "output"))
    )
    (net (code "178") (name "Net-(L1-1)") (class "Default")
      (node (ref "C51") (pin "2") (pinfunction "2_2") (pintype "passive"))
      (node (ref "L1") (pin "P$1") (pinfunction "1_P$1") (pintype "passive"))
      (node (ref "U6") (pin "1") (pinfunction "SW_1") (pintype "power_in"))
      (node (ref "U6") (pin "12") (pinfunction "SW_12") (pintype "power_in"))
      (node (ref "U6") (pin "13") (pinfunction "SW_13") (pintype "power_in"))
      (node (ref "U6") (pin "16") (pinfunction "SW_16") (pintype "power_in"))
    )
    (net (code "179") (name "Net-(LED1-PadA)") (class "Default")
      (node (ref "LED1") (pin "A") (pinfunction "A_A") (pintype "passive"))
      (node (ref "R14") (pin "1") (pinfunction "1_1") (pintype "passive"))
    )
    (net (code "180") (name "Net-(LED2-PadA)") (class "Default")
      (node (ref "LED2") (pin "A") (pinfunction "A_A") (pintype "passive"))
      (node (ref "R16") (pin "1") (pinfunction "1_1") (pintype "passive"))
    )
    (net (code "181") (name "Net-(LED3-PadA)") (class "Default")
      (node (ref "LED3") (pin "A") (pinfunction "A_A") (pintype "passive"))
      (node (ref "R15") (pin "1") (pinfunction "1_1") (pintype "passive"))
    )
    (net (code "182") (name "Net-(LED4-PadA)") (class "Default")
      (node (ref "LED4") (pin "A") (pinfunction "A_A") (pintype "passive"))
      (node (ref "R11") (pin "1") (pinfunction "1_1") (pintype "passive"))
    )
    (net (code "183") (name "Net-(LED5-PadA)") (class "Default")
      (node (ref "LED5") (pin "A") (pinfunction "A_A") (pintype "passive"))
      (node (ref "R19") (pin "1") (pinfunction "1_1") (pintype "passive"))
    )
    (net (code "184") (name "Net-(LED6-PadA)") (class "Default")
      (node (ref "LED6") (pin "A") (pinfunction "A_A") (pintype "passive"))
      (node (ref "R20") (pin "1") (pinfunction "1_1") (pintype "passive"))
    )
    (net (code "185") (name "Net-(LED7-PadA)") (class "Default")
      (node (ref "LED7") (pin "A") (pinfunction "A_A") (pintype "passive"))
      (node (ref "R21") (pin "1") (pinfunction "1_1") (pintype "passive"))
    )
    (net (code "186") (name "Net-(LED8-PadC)") (class "Default")
      (node (ref "LED8") (pin "C") (pinfunction "C_C") (pintype "passive"))
      (node (ref "R45") (pin "2") (pinfunction "2_2") (pintype "passive"))
    )
    (net (code "187") (name "Net-(LED9-PadA)") (class "Default")
      (node (ref "LED9") (pin "A") (pinfunction "A_A") (pintype "passive"))
      (node (ref "R25") (pin "1") (pinfunction "1_1") (pintype "passive"))
    )
    (net (code "188") (name "Net-(Q4-C)") (class "Default")
      (node (ref "LED6") (pin "C") (pinfunction "C_C") (pintype "passive"))
      (node (ref "Q4") (pin "3") (pinfunction "C_3") (pintype "passive"))
      (node (ref "X5") (pin "2") (pinfunction "S_2") (pintype "passive"))
    )
    (net (code "189") (name "Net-(Q5-C)") (class "Default")
      (node (ref "LED7") (pin "C") (pinfunction "C_C") (pintype "passive"))
      (node (ref "Q5") (pin "3") (pinfunction "C_3") (pintype "passive"))
      (node (ref "X6") (pin "2") (pinfunction "S_2") (pintype "passive"))
    )
    (net (code "190") (name "Net-(Q6-C)") (class "Default")
      (node (ref "LED9") (pin "C") (pinfunction "C_C") (pintype "passive"))
      (node (ref "Q6") (pin "3") (pinfunction "C_3") (pintype "passive"))
      (node (ref "X9") (pin "2") (pinfunction "S_2") (pintype "passive"))
    )
    (net (code "191") (name "Net-(Q7-C)") (class "Default")
      (node (ref "LED5") (pin "C") (pinfunction "C_C") (pintype "passive"))
      (node (ref "Q7") (pin "3") (pinfunction "C_3") (pintype "passive"))
      (node (ref "X4") (pin "2") (pinfunction "S_2") (pintype "passive"))
    )
    (net (code "192") (name "Net-(U1-~{SRCLR})") (class "Default")
      (node (ref "R12") (pin "1") (pinfunction "1_1") (pintype "passive"))
      (node (ref "U1") (pin "10") (pinfunction "~{SRCLR}_10") (pintype "input"))
    )
    (net (code "193") (name "Net-(U2-~{SRCLR})") (class "Default")
      (node (ref "R5") (pin "1") (pinfunction "1_1") (pintype "passive"))
      (node (ref "U2") (pin "10") (pinfunction "~{SRCLR}_10") (pintype "input"))
    )
    (net (code "194") (name "Net-(U3-~{SRCLR})") (class "Default")
      (node (ref "R26") (pin "1") (pinfunction "1_1") (pintype "passive"))
      (node (ref "U3") (pin "10") (pinfunction "~{SRCLR}_10") (pintype "input"))
    )
    (net (code "195") (name "Net-(U4-~{SRCLR})") (class "Default")
      (node (ref "R33") (pin "1") (pinfunction "1_1") (pintype "passive"))
      (node (ref "U4") (pin "10") (pinfunction "~{SRCLR}_10") (pintype "input"))
    )
    (net (code "196") (name "Net-(U5-~{SRCLR})") (class "Default")
      (node (ref "R34") (pin "1") (pinfunction "1_1") (pintype "passive"))
      (node (ref "U5") (pin "10") (pinfunction "~{SRCLR}_10") (pintype "input"))
    )
    (net (code "197") (name "Net-(U6-BOOST)") (class "Default")
      (node (ref "R58") (pin "2") (pinfunction "2_2") (pintype "passive"))
      (node (ref "U6") (pin "10") (pinfunction "BOOST_10") (pintype "bidirectional"))
    )
    (net (code "198") (name "Net-(U6-PG)") (class "Default")
      (node (ref "R41") (pin "1") (pinfunction "1_1") (pintype "passive"))
      (node (ref "U6") (pin "8") (pinfunction "PG_8") (pintype "output"))
    )
    (net (code "199") (name "Net-(U10-BOOT)") (class "Default")
      (node (ref "C55") (pin "1") (pinfunction "1_1") (pintype "passive"))
      (node (ref "U10") (pin "2") (pinfunction "BOOT_2") (pintype "input"))
    )
    (net (code "200") (name "Net-(U10-COMP)") (class "Default")
      (node (ref "C56") (pin "1") (pinfunction "1_1") (pintype "passive"))
      (node (ref "U10") (pin "8") (pinfunction "COMP_8") (pintype "bidirectional"))
    )
    (net (code "201") (name "Net-(U10-FB)") (class "Default")
      (node (ref "R42") (pin "2") (pinfunction "2_2") (pintype "passive"))
      (node (ref "R43") (pin "1") (pinfunction "1_1") (pintype "passive"))
      (node (ref "U10") (pin "7") (pinfunction "FB_7") (pintype "input"))
    )
    (net (code "202") (name "Net-(U10-SS)") (class "Default")
      (node (ref "C54") (pin "1") (pinfunction "1_1") (pintype "passive"))
      (node (ref "U10") (pin "10") (pinfunction "SS_10") (pintype "bidirectional"))
    )
    (net (code "203") (name "Net-(U10-SW)") (class "Default")
      (node (ref "C55") (pin "2") (pinfunction "2_2") (pintype "passive"))
      (node (ref "D4") (pin "C") (pinfunction "C_C") (pintype "passive"))
      (node (ref "L2") (pin "P$2") (pinfunction "P$2_P$2") (pintype "passive"))
      (node (ref "U10") (pin "5") (pinfunction "SW_5") (pintype "power_in"))
    )
    (net (code "204") (name "Net-(X3B-1)") (class "Default")
      (node (ref "C59") (pin "1") (pinfunction "1_1") (pintype "passive"))
      (node (ref "D1") (pin "A") (pinfunction "A_A") (pintype "passive"))
      (node (ref "LED3") (pin "C") (pinfunction "C_C") (pintype "passive"))
      (node (ref "Q3") (pin "5") (pinfunction "D_5") (pintype "passive"))
      (node (ref "Q3") (pin "6") (pinfunction "D_6") (pintype "passive"))
      (node (ref "Q3") (pin "7") (pinfunction "D_7") (pintype "passive"))
      (node (ref "Q3") (pin "8") (pinfunction "D_8") (pintype "passive"))
      (node (ref "Q3") (pin "TH") (pinfunction "D_TH") (pintype "passive"))
      (node (ref "R55") (pin "1") (pinfunction "1_1") (pintype "passive"))
      (node (ref "X3") (pin "2") (pinfunction "1_2") (pintype "passive"))
    )
    (net (code "205") (name "Net-(X7B-S)") (class "Default")
      (node (ref "R17") (pin "1") (pinfunction "1_1") (pintype "passive"))
      (node (ref "R39") (pin "1") (pinfunction "1_1") (pintype "passive"))
      (node (ref "X7") (pin "2") (pinfunction "S_2") (pintype "passive"))
    )
    (net (code "206") (name "Net-(X8B-S)") (class "Default")
      (node (ref "R13") (pin "1") (pinfunction "1_1") (pintype "passive"))
      (node (ref "R38") (pin "1") (pinfunction "1_1") (pintype "passive"))
      (node (ref "X8") (pin "2") (pinfunction "S_2") (pintype "passive"))
    )
    (net (code "207") (name "Net-(X11B-S)") (class "Default")
      (node (ref "R18") (pin "1") (pinfunction "1_1") (pintype "passive"))
      (node (ref "R40") (pin "1") (pinfunction "1_1") (pintype "passive"))
      (node (ref "X11") (pin "2") (pinfunction "S_2") (pintype "passive"))
    )
    (net (code "208") (name "Net-(X20C-1)") (class "Default")
      (node (ref "C58") (pin "1") (pinfunction "1_1") (pintype "passive"))
      (node (ref "D2") (pin "A") (pinfunction "A_A") (pintype "passive"))
      (node (ref "LED2") (pin "C") (pinfunction "C_C") (pintype "passive"))
      (node (ref "Q1") (pin "5") (pinfunction "D_5") (pintype "passive"))
      (node (ref "Q1") (pin "6") (pinfunction "D_6") (pintype "passive"))
      (node (ref "Q1") (pin "7") (pinfunction "D_7") (pintype "passive"))
      (node (ref "Q1") (pin "8") (pinfunction "D_8") (pintype "passive"))
      (node (ref "Q1") (pin "TH") (pinfunction "D_TH") (pintype "passive"))
      (node (ref "R56") (pin "1") (pinfunction "1_1") (pintype "passive"))
      (node (ref "X20") (pin "3") (pinfunction "1_3") (pintype "passive"))
      (node (ref "X20") (pin "4") (pinfunction "1_4") (pintype "passive"))
    )
    (net (code "209") (name "Net-(X21B-1)") (class "Default")
      (node (ref "C57") (pin "1") (pinfunction "1_1") (pintype "passive"))
      (node (ref "D3") (pin "A") (pinfunction "A_A") (pintype "passive"))
      (node (ref "LED1") (pin "C") (pinfunction "C_C") (pintype "passive"))
      (node (ref "Q2") (pin "5") (pinfunction "D_5") (pintype "passive"))
      (node (ref "Q2") (pin "6") (pinfunction "D_6") (pintype "passive"))
      (node (ref "Q2") (pin "7") (pinfunction "D_7") (pintype "passive"))
      (node (ref "Q2") (pin "8") (pinfunction "D_8") (pintype "passive"))
      (node (ref "Q2") (pin "TH") (pinfunction "D_TH") (pintype "passive"))
      (node (ref "R57") (pin "1") (pinfunction "1_1") (pintype "passive"))
      (node (ref "X21") (pin "2") (pinfunction "1_2") (pintype "passive"))
    )
    (net (code "210") (name "unconnected-(IC1-CSN_CFG3-Pad2)") (class "Default")
      (node (ref "IC1") (pin "2") (pinfunction "CSN_CFG3_2") (pintype "bidirectional"))
    )
    (net (code "211") (name "unconnected-(IC1-ENCN_DCO-Pad17)") (class "Default")
      (node (ref "IC1") (pin "17") (pinfunction "ENCN_DCO_17") (pintype "bidirectional"))
    )
    (net (code "212") (name "unconnected-(IC1-SD_MODE-Pad9)") (class "Default")
      (node (ref "IC1") (pin "9") (pinfunction "SD_MODE_9") (pintype "bidirectional"))
    )
    (net (code "213") (name "unconnected-(IC1-SWP_DIAG1-Pad21)") (class "Default")
      (node (ref "IC1") (pin "21") (pinfunction "SWP_DIAG1_21") (pintype "bidirectional"))
    )
    (net (code "214") (name "unconnected-(IC2-CSN_CFG3-Pad2)") (class "Default")
      (node (ref "IC2") (pin "2") (pinfunction "CSN_CFG3_2") (pintype "bidirectional"))
    )
    (net (code "215") (name "unconnected-(IC2-ENCN_DCO-Pad17)") (class "Default")
      (node (ref "IC2") (pin "17") (pinfunction "ENCN_DCO_17") (pintype "bidirectional"))
    )
    (net (code "216") (name "unconnected-(IC2-SD_MODE-Pad9)") (class "Default")
      (node (ref "IC2") (pin "9") (pinfunction "SD_MODE_9") (pintype "bidirectional"))
    )
    (net (code "217") (name "unconnected-(IC2-SWP_DIAG1-Pad21)") (class "Default")
      (node (ref "IC2") (pin "21") (pinfunction "SWP_DIAG1_21") (pintype "bidirectional"))
    )
    (net (code "218") (name "unconnected-(IC5-CSN_CFG3-Pad2)") (class "Default")
      (node (ref "IC5") (pin "2") (pinfunction "CSN_CFG3_2") (pintype "bidirectional"))
    )
    (net (code "219") (name "unconnected-(IC5-ENCN_DCO-Pad17)") (class "Default")
      (node (ref "IC5") (pin "17") (pinfunction "ENCN_DCO_17") (pintype "bidirectional"))
    )
    (net (code "220") (name "unconnected-(IC5-SD_MODE-Pad9)") (class "Default")
      (node (ref "IC5") (pin "9") (pinfunction "SD_MODE_9") (pintype "bidirectional"))
    )
    (net (code "221") (name "unconnected-(IC5-SWP_DIAG1-Pad21)") (class "Default")
      (node (ref "IC5") (pin "21") (pinfunction "SWP_DIAG1_21") (pintype "bidirectional"))
    )
    (net (code "222") (name "unconnected-(IC12-CSN_CFG3-Pad2)") (class "Default")
      (node (ref "IC12") (pin "2") (pinfunction "CSN_CFG3_2") (pintype "bidirectional"))
    )
    (net (code "223") (name "unconnected-(IC12-ENCN_DCO-Pad17)") (class "Default")
      (node (ref "IC12") (pin "17") (pinfunction "ENCN_DCO_17") (pintype "bidirectional"))
    )
    (net (code "224") (name "unconnected-(IC12-SD_MODE-Pad9)") (class "Default")
      (node (ref "IC12") (pin "9") (pinfunction "SD_MODE_9") (pintype "bidirectional"))
    )
    (net (code "225") (name "unconnected-(IC12-SWP_DIAG1-Pad21)") (class "Default")
      (node (ref "IC12") (pin "21") (pinfunction "SWP_DIAG1_21") (pintype "bidirectional"))
    )
    (net (code "226") (name "unconnected-(IC15-CSN_CFG3-Pad2)") (class "Default")
      (node (ref "IC15") (pin "2") (pinfunction "CSN_CFG3_2") (pintype "bidirectional"))
    )
    (net (code "227") (name "unconnected-(IC15-ENCN_DCO-Pad17)") (class "Default")
      (node (ref "IC15") (pin "17") (pinfunction "ENCN_DCO_17") (pintype "bidirectional"))
    )
    (net (code "228") (name "unconnected-(IC15-SD_MODE-Pad9)") (class "Default")
      (node (ref "IC15") (pin "9") (pinfunction "SD_MODE_9") (pintype "bidirectional"))
    )
    (net (code "229") (name "unconnected-(IC15-SWP_DIAG1-Pad21)") (class "Default")
      (node (ref "IC15") (pin "21") (pinfunction "SWP_DIAG1_21") (pintype "bidirectional"))
    )
    (net (code "230") (name "unconnected-(P8-Pad3)") (class "Default")
      (node (ref "P8") (pin "3") (pinfunction "3_3") (pintype "passive"))
    )
    (net (code "231") (name "unconnected-(P8-Pad4)") (class "Default")
      (node (ref "P8") (pin "4") (pinfunction "4_4") (pintype "passive"))
    )
    (net (code "232") (name "unconnected-(P8-Pad5)") (class "Default")
      (node (ref "P8") (pin "5") (pinfunction "5_5") (pintype "passive"))
    )
    (net (code "233") (name "unconnected-(P8-Pad6)") (class "Default")
      (node (ref "P8") (pin "6") (pinfunction "6_6") (pintype "passive"))
    )
    (net (code "234") (name "unconnected-(P8-Pad7)") (class "Default")
      (node (ref "P8") (pin "7") (pinfunction "7_7") (pintype "passive"))
    )
    (net (code "235") (name "unconnected-(P8-Pad20)") (class "Default")
      (node (ref "P8") (pin "20") (pinfunction "20_20") (pintype "passive"))
    )
    (net (code "236") (name "unconnected-(P8-Pad21)") (class "Default")
      (node (ref "P8") (pin "21") (pinfunction "21_21") (pintype "passive"))
    )
    (net (code "237") (name "unconnected-(P8-Pad22)") (class "Default")
      (node (ref "P8") (pin "22") (pinfunction "22_22") (pintype "passive"))
    )
    (net (code "238") (name "unconnected-(P8-Pad23)") (class "Default")
      (node (ref "P8") (pin "23") (pinfunction "23_23") (pintype "passive"))
    )
    (net (code "239") (name "unconnected-(P8-Pad24)") (class "Default")
      (node (ref "P8") (pin "24") (pinfunction "24_24") (pintype "passive"))
    )
    (net (code "240") (name "unconnected-(P8-Pad25)") (class "Default")
      (node (ref "P8") (pin "25") (pinfunction "25_25") (pintype "passive"))
    )
    (net (code "241") (name "unconnected-(P8-Pad27)") (class "Default")
      (node (ref "P8") (pin "27") (pinfunction "27_27") (pintype "passive"))
    )
    (net (code "242") (name "unconnected-(P8-Pad28)") (class "Default")
      (node (ref "P8") (pin "28") (pinfunction "28_28") (pintype "passive"))
    )
    (net (code "243") (name "unconnected-(P8-Pad29)") (class "Default")
      (node (ref "P8") (pin "29") (pinfunction "29_29") (pintype "passive"))
    )
    (net (code "244") (name "unconnected-(P8-Pad30)") (class "Default")
      (node (ref "P8") (pin "30") (pinfunction "30_30") (pintype "passive"))
    )
    (net (code "245") (name "unconnected-(P8-Pad31)") (class "Default")
      (node (ref "P8") (pin "31") (pinfunction "31_31") (pintype "passive"))
    )
    (net (code "246") (name "unconnected-(P8-Pad32)") (class "Default")
      (node (ref "P8") (pin "32") (pinfunction "32_32") (pintype "passive"))
    )
    (net (code "247") (name "unconnected-(P8-Pad33)") (class "Default")
      (node (ref "P8") (pin "33") (pinfunction "33_33") (pintype "passive"))
    )
    (net (code "248") (name "unconnected-(P8-Pad34)") (class "Default")
      (node (ref "P8") (pin "34") (pinfunction "34_34") (pintype "passive"))
    )
    (net (code "249") (name "unconnected-(P8-Pad35)") (class "Default")
      (node (ref "P8") (pin "35") (pinfunction "35_35") (pintype "passive"))
    )
    (net (code "250") (name "unconnected-(P8-Pad36)") (class "Default")
      (node (ref "P8") (pin "36") (pinfunction "36_36") (pintype "passive"))
    )
    (net (code "251") (name "unconnected-(P8-Pad37)") (class "Default")
      (node (ref "P8") (pin "37") (pinfunction "37_37") (pintype "passive"))
    )
    (net (code "252") (name "unconnected-(P8-Pad38)") (class "Default")
      (node (ref "P8") (pin "38") (pinfunction "38_38") (pintype "passive"))
    )
    (net (code "253") (name "unconnected-(P8-Pad39)") (class "Default")
      (node (ref "P8") (pin "39") (pinfunction "39_39") (pintype "passive"))
    )
    (net (code "254") (name "unconnected-(P8-Pad40)") (class "Default")
      (node (ref "P8") (pin "40") (pinfunction "40_40") (pintype "passive"))
    )
    (net (code "255") (name "unconnected-(P8-Pad41)") (class "Default")
      (node (ref "P8") (pin "41") (pinfunction "41_41") (pintype "passive"))
    )
    (net (code "256") (name "unconnected-(P8-Pad42)") (class "Default")
      (node (ref "P8") (pin "42") (pinfunction "42_42") (pintype "passive"))
    )
    (net (code "257") (name "unconnected-(P8-Pad43)") (class "Default")
      (node (ref "P8") (pin "43") (pinfunction "43_43") (pintype "passive"))
    )
    (net (code "258") (name "unconnected-(P8-Pad44)") (class "Default")
      (node (ref "P8") (pin "44") (pinfunction "44_44") (pintype "passive"))
    )
    (net (code "259") (name "unconnected-(P8-Pad45)") (class "Default")
      (node (ref "P8") (pin "45") (pinfunction "45_45") (pintype "passive"))
    )
    (net (code "260") (name "unconnected-(P8-Pad46)") (class "Default")
      (node (ref "P8") (pin "46") (pinfunction "46_46") (pintype "passive"))
    )
    (net (code "261") (name "unconnected-(P9-Pad7)") (class "Default")
      (node (ref "P9") (pin "7") (pinfunction "7_7") (pintype "passive"))
    )
    (net (code "262") (name "unconnected-(P9-Pad9)") (class "Default")
      (node (ref "P9") (pin "9") (pinfunction "9_9") (pintype "passive"))
    )
    (net (code "263") (name "unconnected-(P9-Pad10)") (class "Default")
      (node (ref "P9") (pin "10") (pinfunction "10_10") (pintype "passive"))
    )
    (net (code "264") (name "unconnected-(P9-Pad15)") (class "Default")
      (node (ref "P9") (pin "15") (pinfunction "15_15") (pintype "passive"))
    )
    (net (code "265") (name "unconnected-(P9-Pad17)") (class "Default")
      (node (ref "P9") (pin "17") (pinfunction "17_17") (pintype "passive"))
    )
    (net (code "266") (name "unconnected-(P9-Pad21)") (class "Default")
      (node (ref "P9") (pin "21") (pinfunction "21_21") (pintype "passive"))
    )
    (net (code "267") (name "unconnected-(P9-Pad26)") (class "Default")
      (node (ref "P9") (pin "26") (pinfunction "26_26") (pintype "passive"))
    )
    (net (code "268") (name "unconnected-(P9-Pad27)") (class "Default")
      (node (ref "P9") (pin "27") (pinfunction "27_27") (pintype "passive"))
    )
    (net (code "269") (name "unconnected-(P9-Pad29)") (class "Default")
      (node (ref "P9") (pin "29") (pinfunction "29_29") (pintype "passive"))
    )
    (net (code "270") (name "unconnected-(P9-Pad34)") (class "Default")
      (node (ref "P9") (pin "34") (pinfunction "34_34") (pintype "passive"))
    )
    (net (code "271") (name "unconnected-(P9-Pad37)") (class "Default")
      (node (ref "P9") (pin "37") (pinfunction "37_37") (pintype "passive"))
    )
    (net (code "272") (name "unconnected-(P9-Pad38)") (class "Default")
      (node (ref "P9") (pin "38") (pinfunction "38_38") (pintype "passive"))
    )
    (net (code "273") (name "unconnected-(P9-Pad39)") (class "Default")
      (node (ref "P9") (pin "39") (pinfunction "39_39") (pintype "passive"))
    )
    (net (code "274") (name "unconnected-(P9-Pad40)") (class "Default")
      (node (ref "P9") (pin "40") (pinfunction "40_40") (pintype "passive"))
    )
    (net (code "275") (name "unconnected-(U1-QA-Pad15)") (class "Default")
      (node (ref "U1") (pin "15") (pinfunction "QA_15") (pintype "output"))
    )
    (net (code "276") (name "unconnected-(U2-QA-Pad15)") (class "Default")
      (node (ref "U2") (pin "15") (pinfunction "QA_15") (pintype "output"))
    )
    (net (code "277") (name "unconnected-(U5-QA-Pad15)") (class "Default")
      (node (ref "U5") (pin "15") (pinfunction "QA_15") (pintype "output"))
    )
    (net (code "278") (name "unconnected-(U5-QH_2-Pad9)") (class "Default")
      (node (ref "U5") (pin "9") (pinfunction "QH_2_9") (pintype "output"))
    )
    (net (code "279") (name "unconnected-(U6-EN-Pad9)") (class "Default")
      (node (ref "U6") (pin "9") (pinfunction "EN_9") (pintype "input"))
    )
    (net (code "280") (name "unconnected-(U10-EN-Pad9)") (class "Default")
      (node (ref "U10") (pin "9") (pinfunction "EN_9") (pintype "input"))
    )
    (net (code "281") (name "unconnected-(U11-EXTCLK-Pad25)") (class "Default")
      (node (ref "U11") (pin "25") (pinfunction "EXTCLK_25") (pintype "input"))
    )
    (net (code "282") (name "unconnected-(U11-LED0-Pad6)") (class "Default")
      (node (ref "U11") (pin "6") (pinfunction "LED0_6") (pintype "output"))
    )
    (net (code "283") (name "unconnected-(U11-LED1-Pad7)") (class "Default")
      (node (ref "U11") (pin "7") (pinfunction "LED1_7") (pintype "output"))
    )
    (net (code "284") (name "unconnected-(U11-LED2-Pad8)") (class "Default")
      (node (ref "U11") (pin "8") (pinfunction "LED2_8") (pintype "output"))
    )
    (net (code "285") (name "unconnected-(U11-LED6-Pad12)") (class "Default")
      (node (ref "U11") (pin "12") (pinfunction "LED6_12") (pintype "output"))
    )
    (net (code "286") (name "unconnected-(U18-~{WC}-Pad7)") (class "Default")
      (node (ref "U18") (pin "7") (pinfunction "~{WC}_7") (pintype "no_connect"))
    )
    (net (code "287") (name "unconnected-(U19-NC-Pad16)") (class "Default")
      (node (ref "U19") (pin "16") (pinfunction "NC_16") (pintype "no_connect"))
    )
    (net (code "288") (name "unconnected-(U19-NC_2-Pad13)") (class "Default")
      (node (ref "U19") (pin "13") (pinfunction "NC_2_13") (pintype "no_connect"))
    )
  )
)
